# RFWBBoard.net
KiCad netlist of a schematic drawn in EAGLE
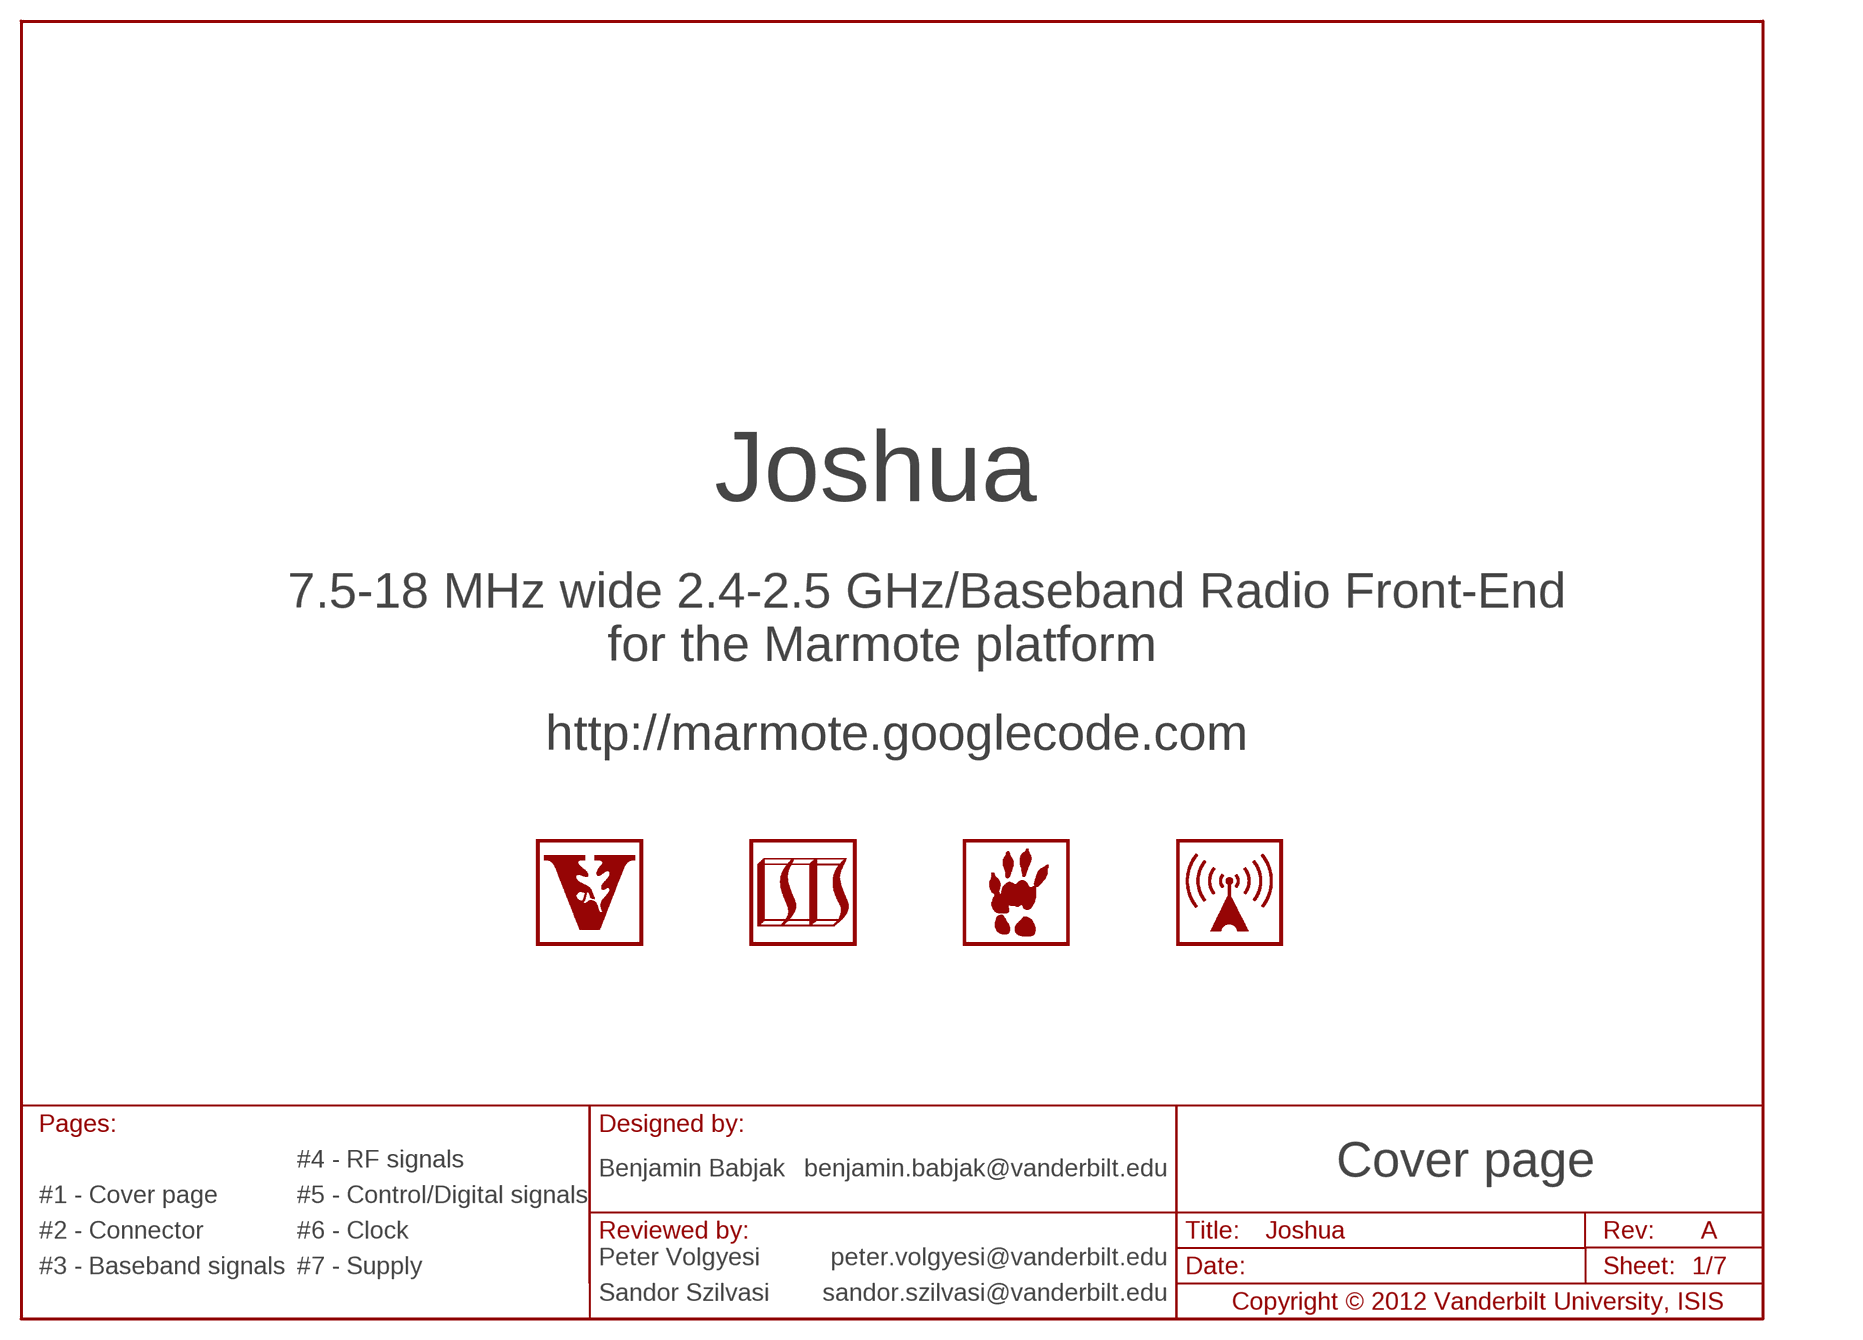
[diagram p0: schematic, sheet 1]
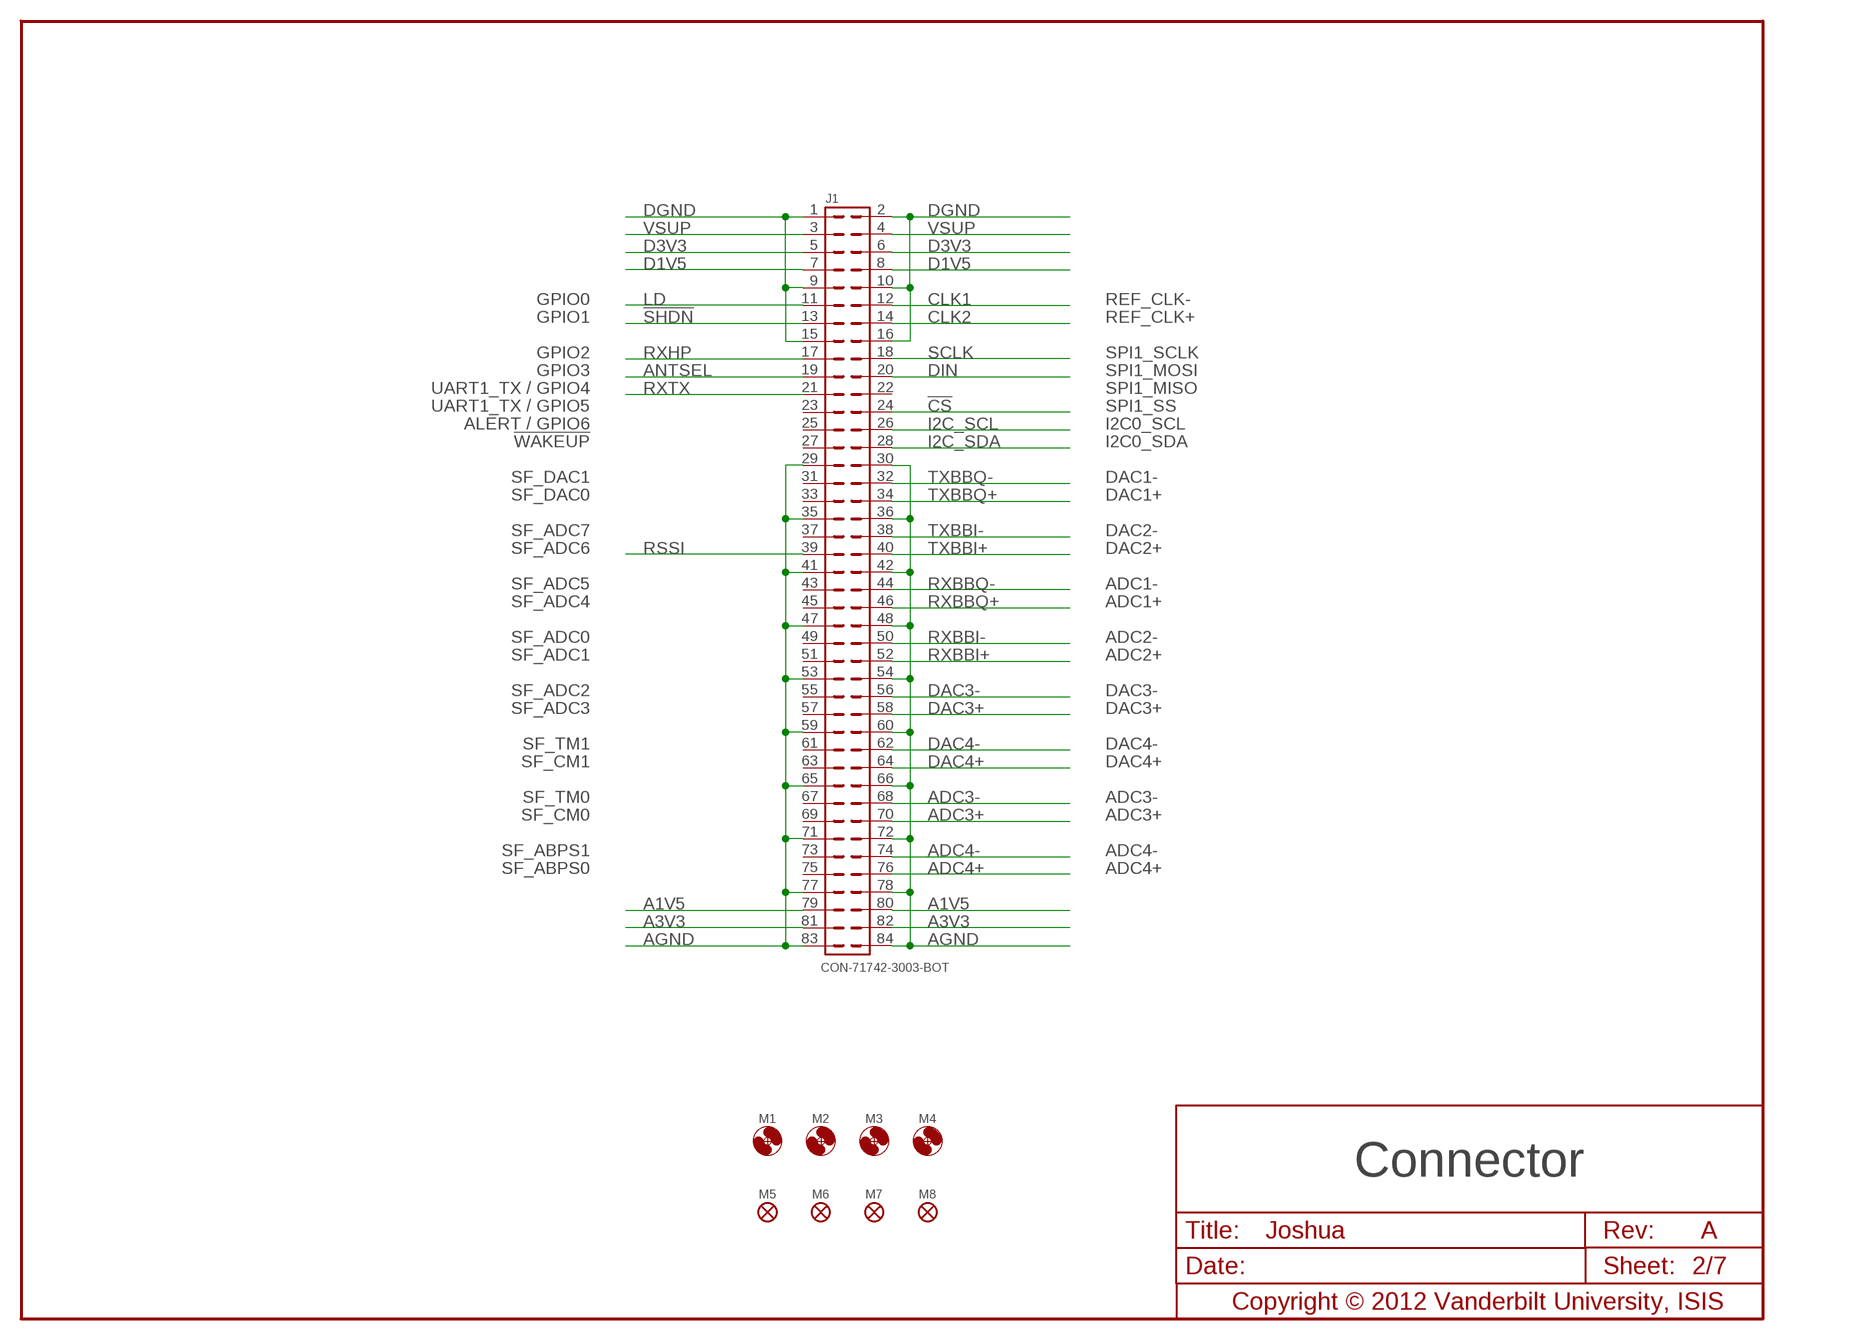
[diagram p1: schematic, sheet 2]
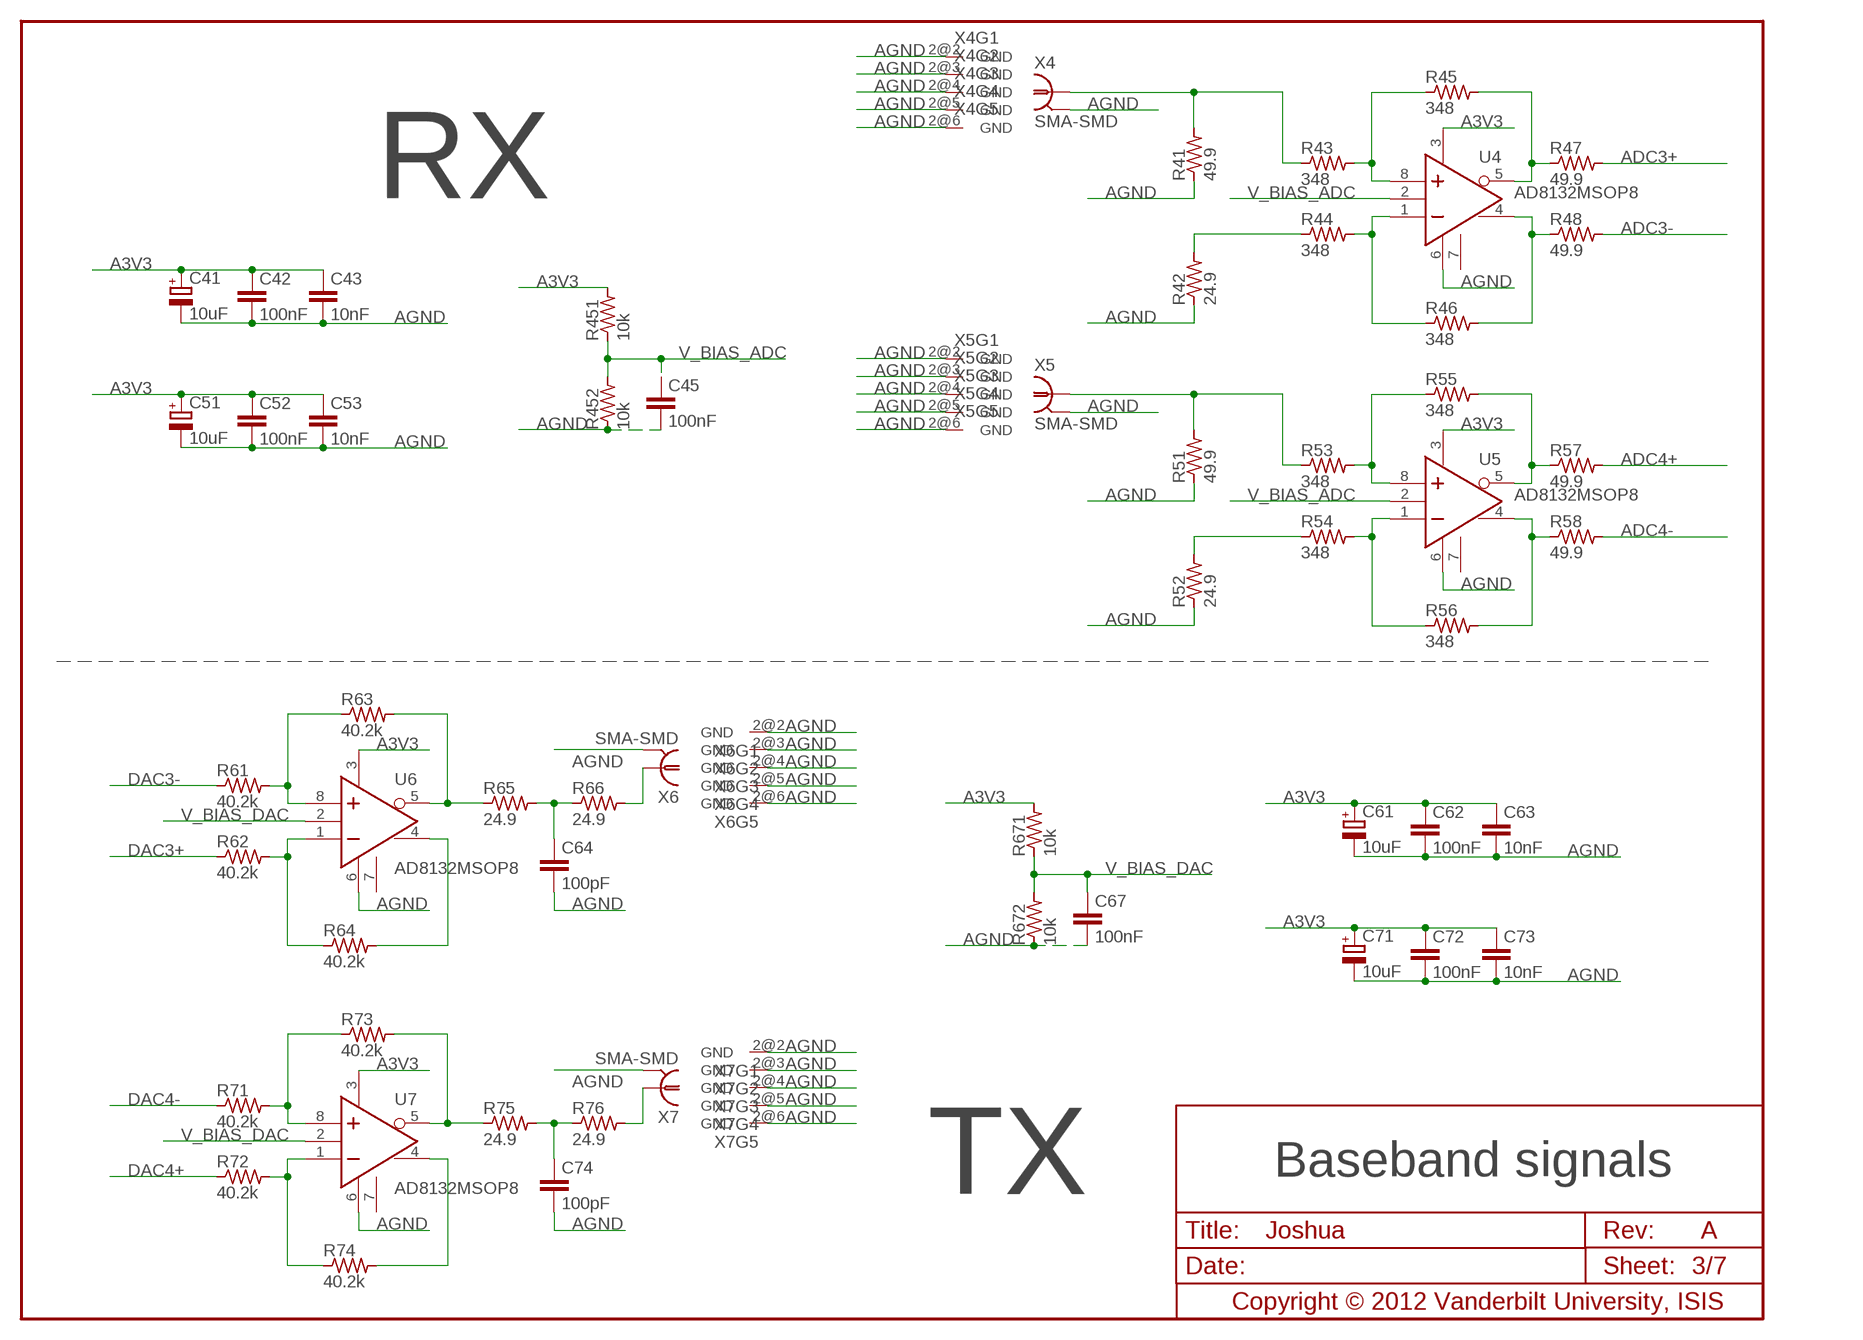
[diagram p2: schematic, sheet 3]
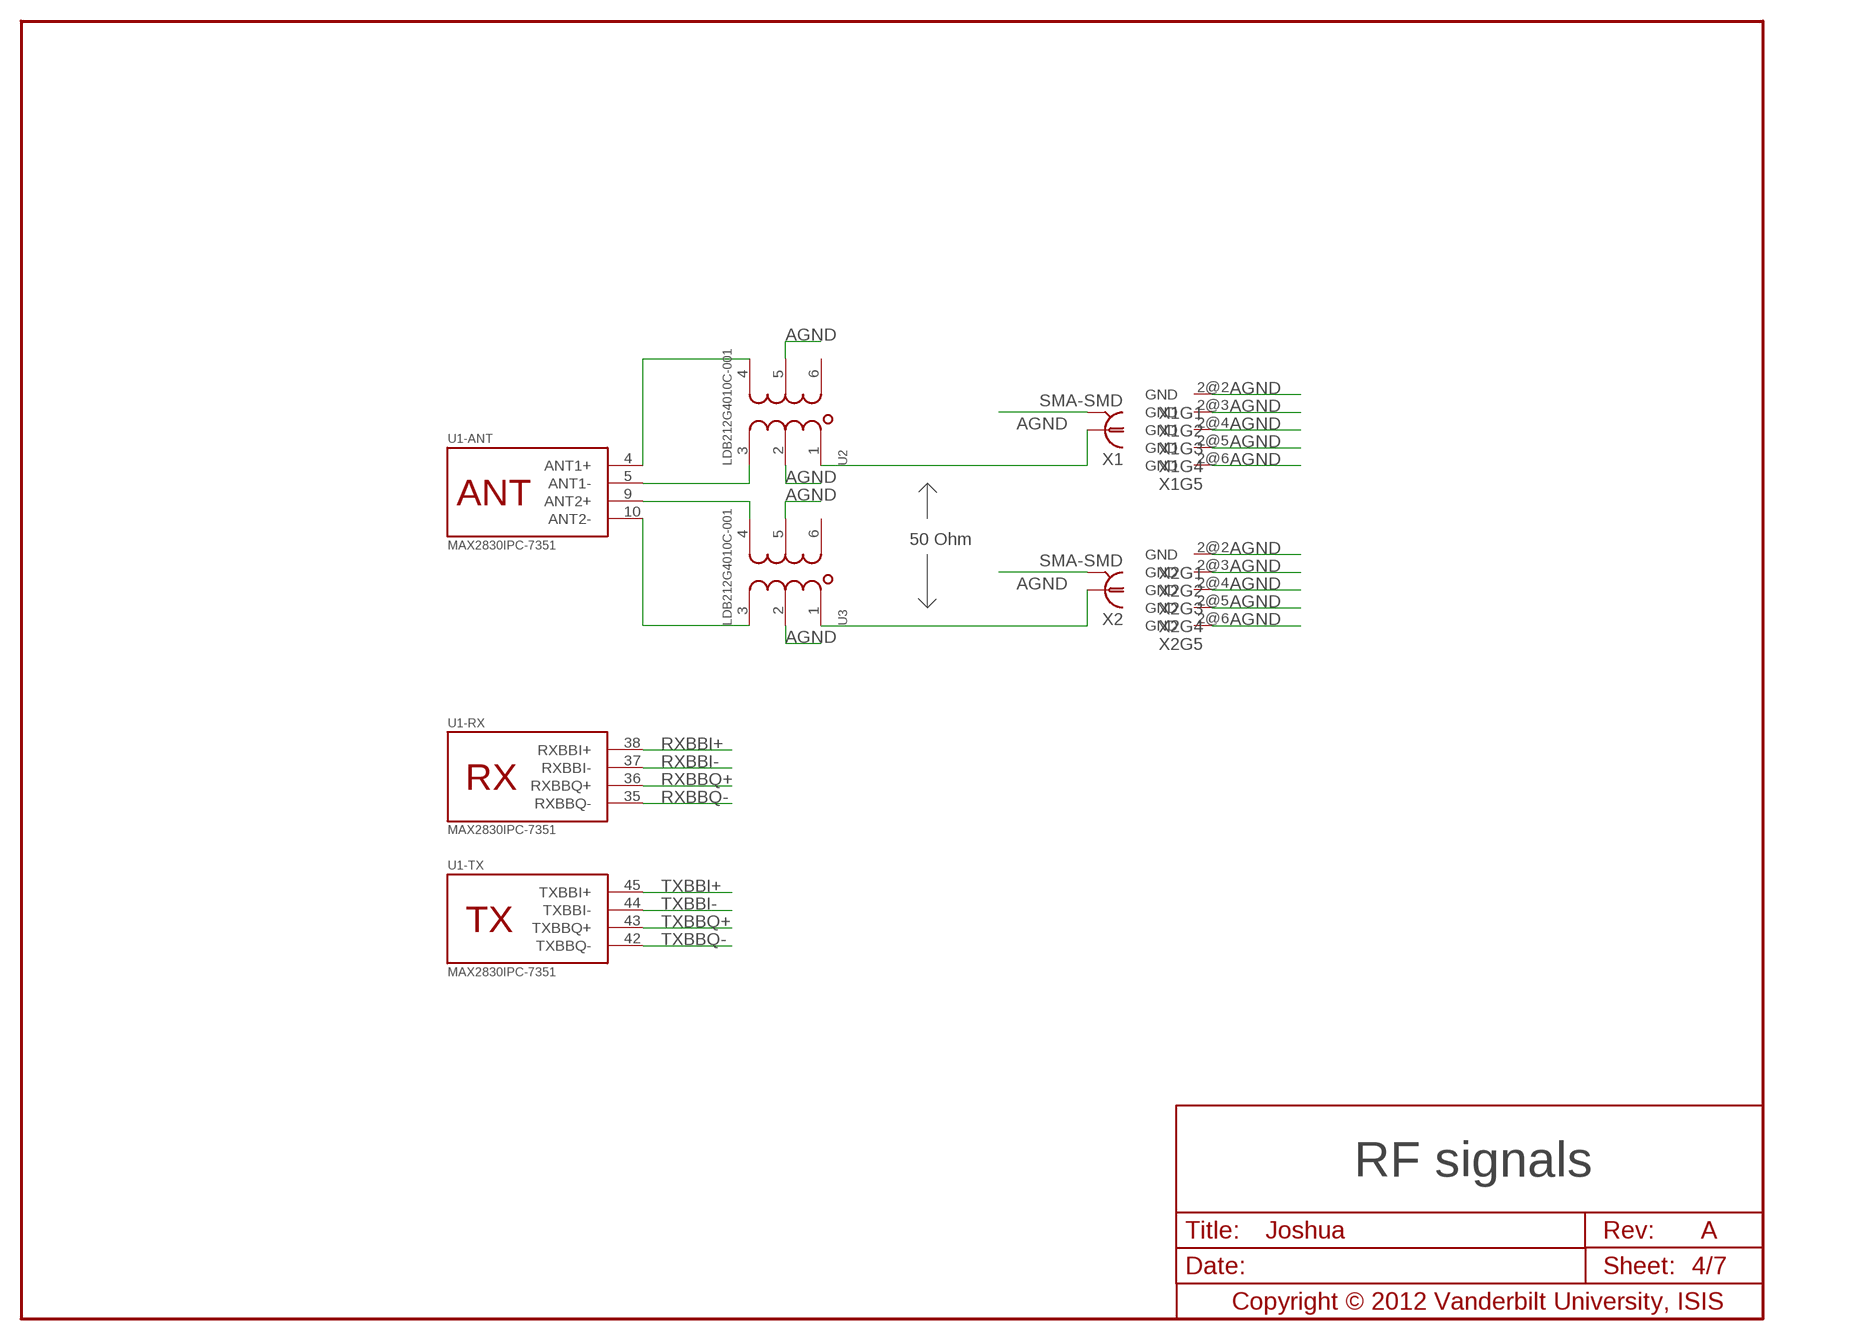
[diagram p3: schematic, sheet 4]
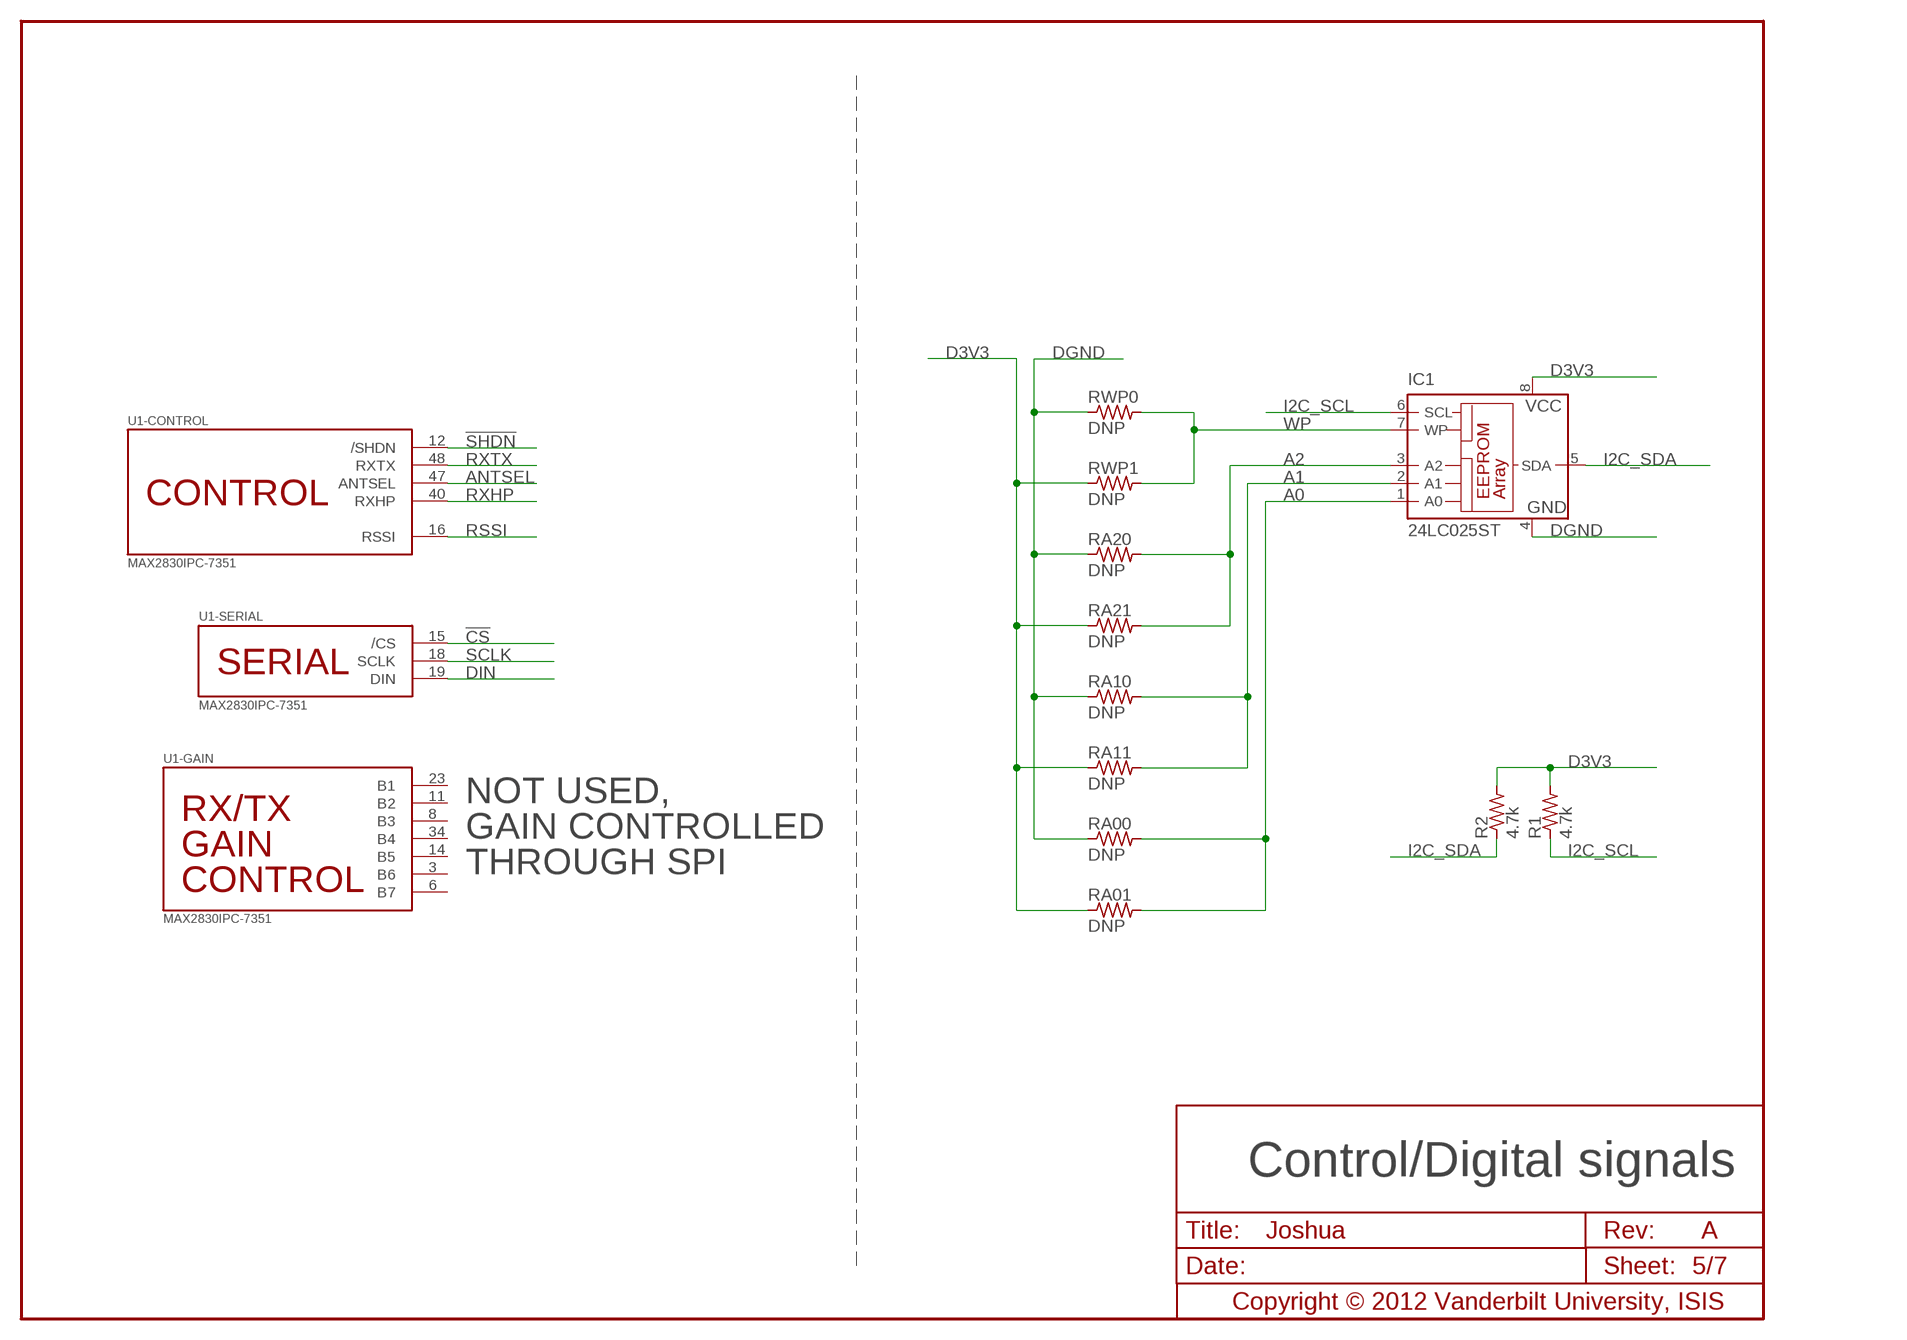
[diagram p4: schematic, sheet 5]
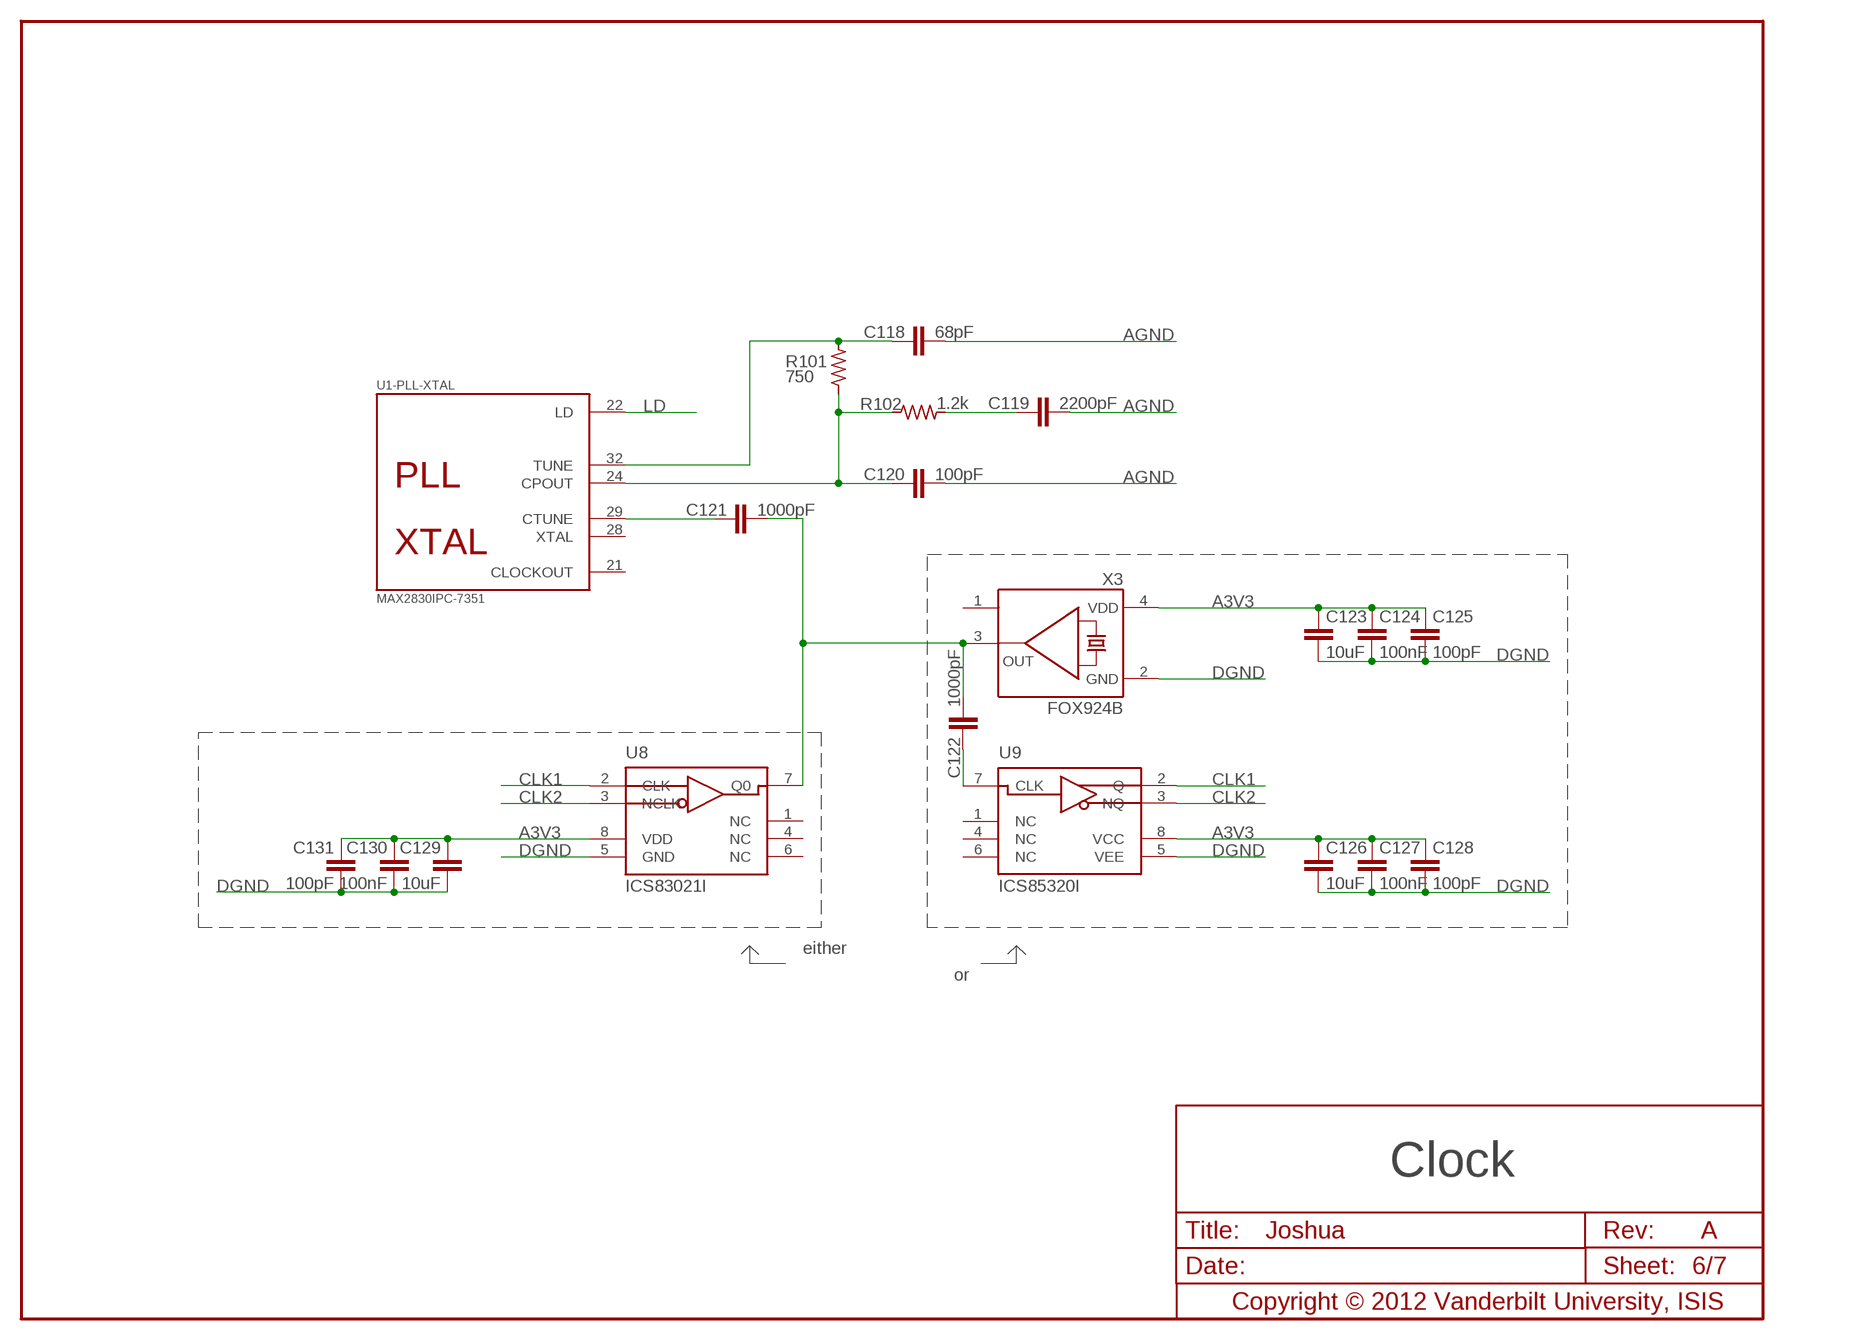
[diagram p5: schematic, sheet 6]
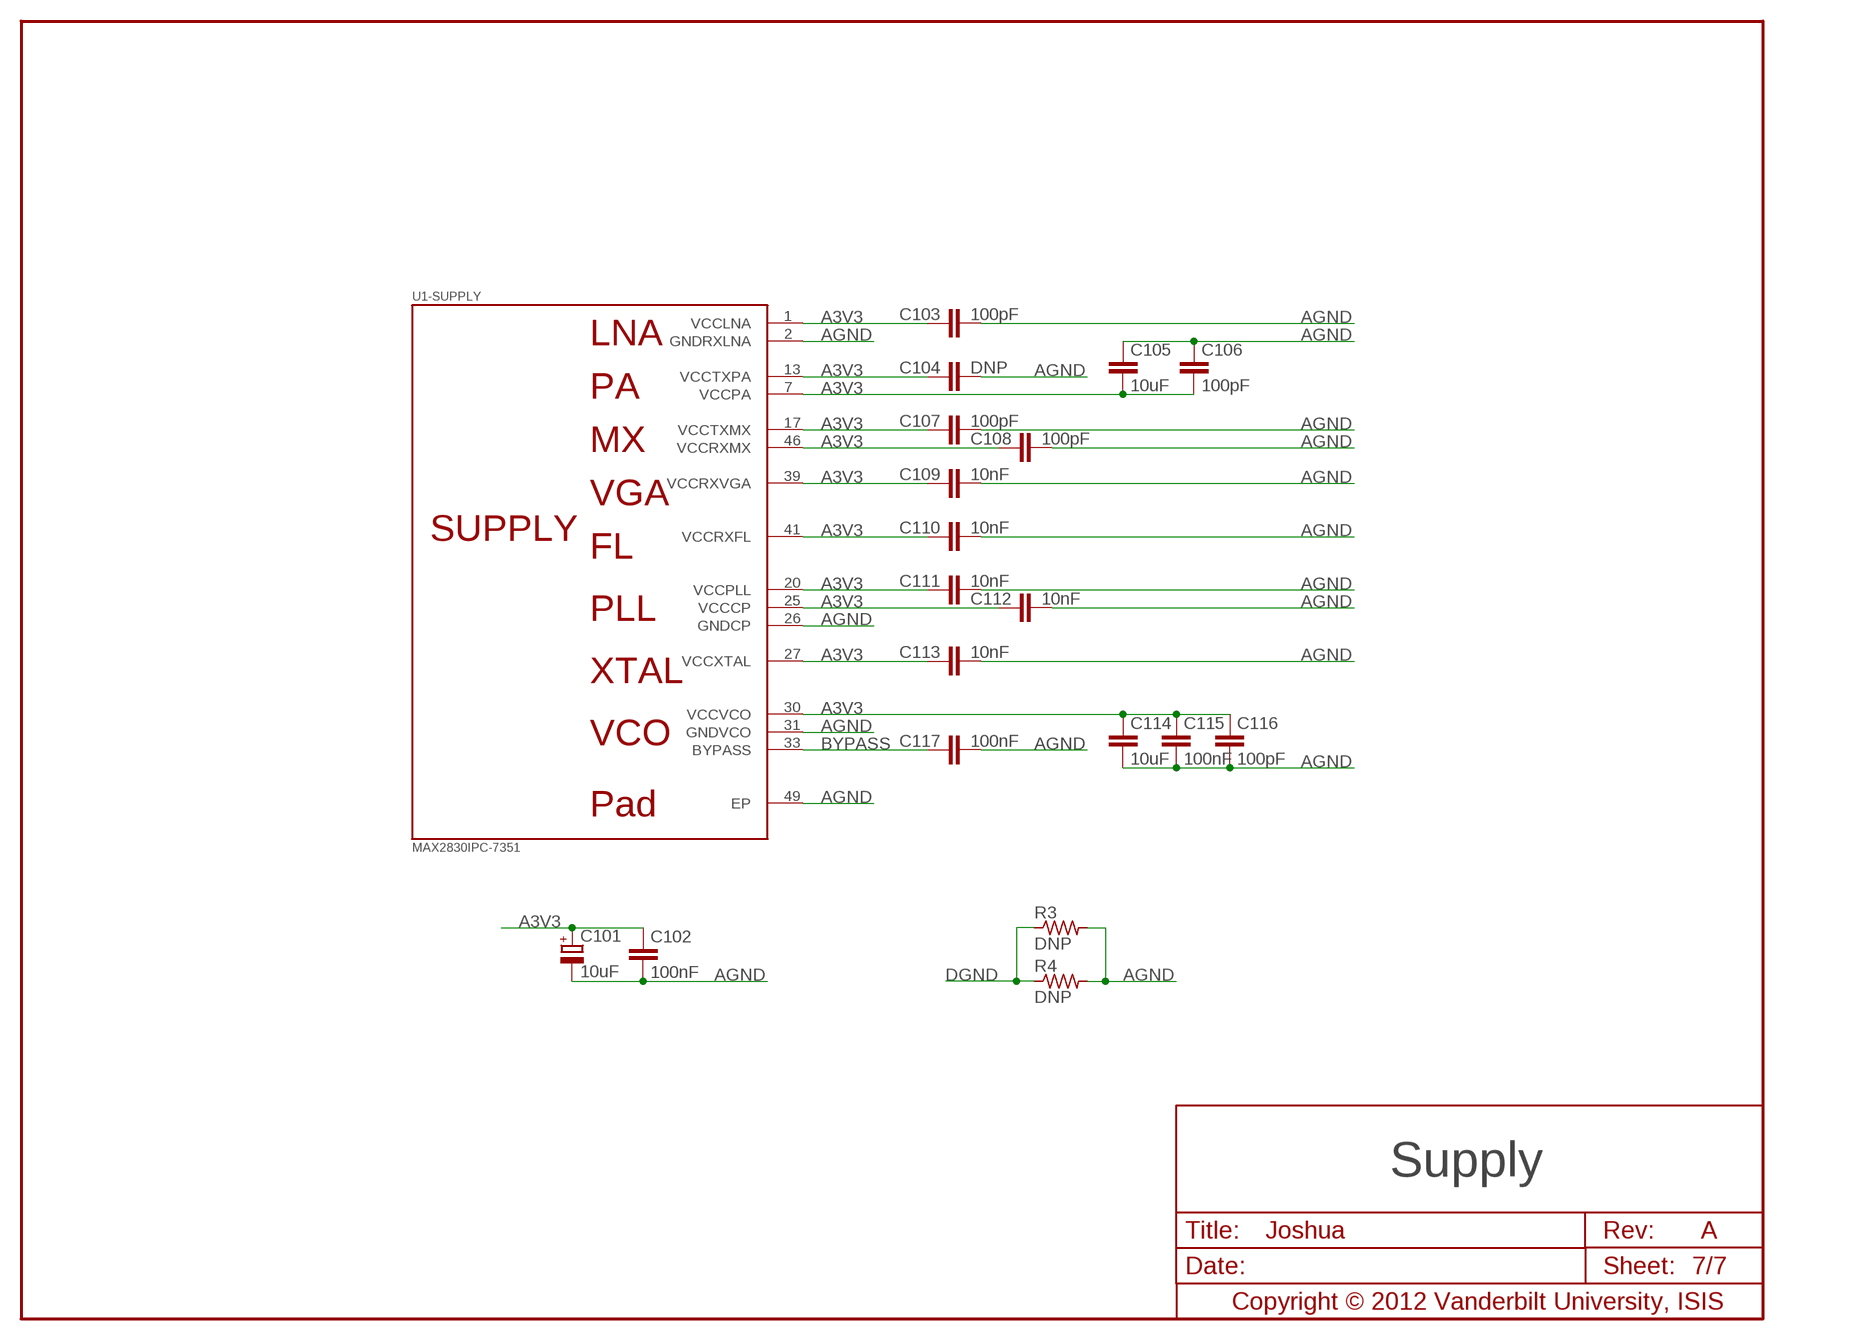
[diagram p6: schematic, sheet 7]

(export (version "E")
  (design (tool "Eeschema 10.0.6"))
  (components
    (comp (ref "J1")
      (value "CON-71742-3003-BOT")
      (footprint "eagle-import:71742-3003-BOT")
      (libsource (lib "eagle-import") (part "CON-71742-3003-BOT"))
    )
    (comp (ref "M1")
      (value "MOUNT-HOLE3.3")
      (footprint "eagle-import:3,3")
      (libsource (lib "eagle-import") (part "MOUNT-HOLE3.3"))
    )
    (comp (ref "M2")
      (value "MOUNT-HOLE3.3")
      (footprint "eagle-import:3,3")
      (libsource (lib "eagle-import") (part "MOUNT-HOLE3.3"))
    )
    (comp (ref "M3")
      (value "MOUNT-HOLE3.3")
      (footprint "eagle-import:3,3")
      (libsource (lib "eagle-import") (part "MOUNT-HOLE3.3"))
    )
    (comp (ref "M4")
      (value "MOUNT-HOLE3.3")
      (footprint "eagle-import:3,3")
      (libsource (lib "eagle-import") (part "MOUNT-HOLE3.3"))
    )
    (comp (ref "M5")
      (value "FIDUCIAL1X2")
      (footprint "eagle-import:FIDUCIAL-1X2")
      (libsource (lib "eagle-import") (part "FIDUCIAL1X2"))
    )
    (comp (ref "M6")
      (value "FIDUCIAL1X2")
      (footprint "eagle-import:FIDUCIAL-1X2")
      (libsource (lib "eagle-import") (part "FIDUCIAL1X2"))
    )
    (comp (ref "M7")
      (value "FIDUCIAL1X2")
      (footprint "eagle-import:FIDUCIAL-1X2")
      (libsource (lib "eagle-import") (part "FIDUCIAL1X2"))
    )
    (comp (ref "M8")
      (value "FIDUCIAL1X2")
      (footprint "eagle-import:FIDUCIAL-1X2")
      (libsource (lib "eagle-import") (part "FIDUCIAL1X2"))
    )
    (comp (ref "LOGO4")
      (value "LOGO-ISIS-600MIL-10MM-SS")
      (footprint "eagle-import:LOGO-ISIS-10MM-SILKSCREEN")
      (libsource (lib "eagle-import") (part "LOGO-ISIS-600MIL-10MM-SS"))
    )
    (comp (ref "LOGO5")
      (value "LOGO-VANDERBILT-600MIL-10MM-SS")
      (footprint "eagle-import:LOGO-VANDERBILT-10MM-SILKSCREEN")
      (libsource (lib "eagle-import") (part "LOGO-VANDERBILT-600MIL-10MM-SS"))
    )
    (comp (ref "LOGO6")
      (value "LOGO-MARMOTE-600MIL-10MM-SS")
      (footprint "eagle-import:LOGO-MARMOTE-10MM-SILKSCREEN")
      (libsource (lib "eagle-import") (part "LOGO-MARMOTE-600MIL-10MM-SS"))
    )
    (comp (ref "LOGO7")
      (value "LOGO-RADIO-3-600MIL-10MM-SS")
      (footprint "eagle-import:LOGO-RADIO-FILLED-10MM-SILKSCREEN")
      (libsource (lib "eagle-import") (part "LOGO-RADIO-3-600MIL-10MM-SS"))
    )
    (comp (ref "C41")
      (value "10uF")
      (footprint "eagle-import:CPOL2012")
      (libsource (lib "eagle-import") (part "CPOL2012"))
    )
    (comp (ref "C42")
      (value "100nF")
      (footprint "eagle-import:C0402")
      (libsource (lib "eagle-import") (part "C0402"))
    )
    (comp (ref "C43")
      (value "10nF")
      (footprint "eagle-import:C0402")
      (libsource (lib "eagle-import") (part "C0402"))
    )
    (comp (ref "C45")
      (value "100nF")
      (footprint "eagle-import:C0402")
      (libsource (lib "eagle-import") (part "C0402"))
    )
    (comp (ref "C51")
      (value "10uF")
      (footprint "eagle-import:CPOL2012")
      (libsource (lib "eagle-import") (part "CPOL2012"))
    )
    (comp (ref "C52")
      (value "100nF")
      (footprint "eagle-import:C0402")
      (libsource (lib "eagle-import") (part "C0402"))
    )
    (comp (ref "C53")
      (value "10nF")
      (footprint "eagle-import:C0402")
      (libsource (lib "eagle-import") (part "C0402"))
    )
    (comp (ref "C61")
      (value "10uF")
      (footprint "eagle-import:CPOL2012")
      (libsource (lib "eagle-import") (part "CPOL2012"))
    )
    (comp (ref "C62")
      (value "100nF")
      (footprint "eagle-import:C0402")
      (libsource (lib "eagle-import") (part "C0402"))
    )
    (comp (ref "C63")
      (value "10nF")
      (footprint "eagle-import:C0402")
      (libsource (lib "eagle-import") (part "C0402"))
    )
    (comp (ref "C64")
      (value "100pF")
      (footprint "eagle-import:C0402")
      (libsource (lib "eagle-import") (part "C0402"))
    )
    (comp (ref "C67")
      (value "100nF")
      (footprint "eagle-import:C0402")
      (libsource (lib "eagle-import") (part "C0402"))
    )
    (comp (ref "C71")
      (value "10uF")
      (footprint "eagle-import:CPOL2012")
      (libsource (lib "eagle-import") (part "CPOL2012"))
    )
    (comp (ref "C72")
      (value "100nF")
      (footprint "eagle-import:C0402")
      (libsource (lib "eagle-import") (part "C0402"))
    )
    (comp (ref "C73")
      (value "10nF")
      (footprint "eagle-import:C0402")
      (libsource (lib "eagle-import") (part "C0402"))
    )
    (comp (ref "C74")
      (value "100pF")
      (footprint "eagle-import:C0402")
      (libsource (lib "eagle-import") (part "C0402"))
    )
    (comp (ref "R41")
      (value "49.9")
      (footprint "eagle-import:R0402")
      (libsource (lib "eagle-import") (part "R0402"))
    )
    (comp (ref "R42")
      (value "24.9")
      (footprint "eagle-import:R0402")
      (libsource (lib "eagle-import") (part "R0402"))
    )
    (comp (ref "R43")
      (value "348")
      (footprint "eagle-import:R0402")
      (libsource (lib "eagle-import") (part "R0402"))
    )
    (comp (ref "R44")
      (value "348")
      (footprint "eagle-import:R0402")
      (libsource (lib "eagle-import") (part "R0402"))
    )
    (comp (ref "R45")
      (value "348")
      (footprint "eagle-import:R0402")
      (libsource (lib "eagle-import") (part "R0402"))
    )
    (comp (ref "R46")
      (value "348")
      (footprint "eagle-import:R0402")
      (libsource (lib "eagle-import") (part "R0402"))
    )
    (comp (ref "R47")
      (value "49.9")
      (footprint "eagle-import:R0402")
      (libsource (lib "eagle-import") (part "R0402"))
    )
    (comp (ref "R48")
      (value "49.9")
      (footprint "eagle-import:R0402")
      (libsource (lib "eagle-import") (part "R0402"))
    )
    (comp (ref "R51")
      (value "49.9")
      (footprint "eagle-import:R0402")
      (libsource (lib "eagle-import") (part "R0402"))
    )
    (comp (ref "R52")
      (value "24.9")
      (footprint "eagle-import:R0402")
      (libsource (lib "eagle-import") (part "R0402"))
    )
    (comp (ref "R53")
      (value "348")
      (footprint "eagle-import:R0402")
      (libsource (lib "eagle-import") (part "R0402"))
    )
    (comp (ref "R54")
      (value "348")
      (footprint "eagle-import:R0402")
      (libsource (lib "eagle-import") (part "R0402"))
    )
    (comp (ref "R55")
      (value "348")
      (footprint "eagle-import:R0402")
      (libsource (lib "eagle-import") (part "R0402"))
    )
    (comp (ref "R56")
      (value "348")
      (footprint "eagle-import:R0402")
      (libsource (lib "eagle-import") (part "R0402"))
    )
    (comp (ref "R57")
      (value "49.9")
      (footprint "eagle-import:R0402")
      (libsource (lib "eagle-import") (part "R0402"))
    )
    (comp (ref "R58")
      (value "49.9")
      (footprint "eagle-import:R0402")
      (libsource (lib "eagle-import") (part "R0402"))
    )
    (comp (ref "R61")
      (value "40.2k")
      (footprint "eagle-import:R0402")
      (libsource (lib "eagle-import") (part "R0402"))
    )
    (comp (ref "R62")
      (value "40.2k")
      (footprint "eagle-import:R0402")
      (libsource (lib "eagle-import") (part "R0402"))
    )
    (comp (ref "R63")
      (value "40.2k")
      (footprint "eagle-import:R0402")
      (libsource (lib "eagle-import") (part "R0402"))
    )
    (comp (ref "R64")
      (value "40.2k")
      (footprint "eagle-import:R0402")
      (libsource (lib "eagle-import") (part "R0402"))
    )
    (comp (ref "R65")
      (value "24.9")
      (footprint "eagle-import:R0402")
      (libsource (lib "eagle-import") (part "R0402"))
    )
    (comp (ref "R66")
      (value "24.9")
      (footprint "eagle-import:R0402")
      (libsource (lib "eagle-import") (part "R0402"))
    )
    (comp (ref "R71")
      (value "40.2k")
      (footprint "eagle-import:R0402")
      (libsource (lib "eagle-import") (part "R0402"))
    )
    (comp (ref "R72")
      (value "40.2k")
      (footprint "eagle-import:R0402")
      (libsource (lib "eagle-import") (part "R0402"))
    )
    (comp (ref "R73")
      (value "40.2k")
      (footprint "eagle-import:R0402")
      (libsource (lib "eagle-import") (part "R0402"))
    )
    (comp (ref "R74")
      (value "40.2k")
      (footprint "eagle-import:R0402")
      (libsource (lib "eagle-import") (part "R0402"))
    )
    (comp (ref "R75")
      (value "24.9")
      (footprint "eagle-import:R0402")
      (libsource (lib "eagle-import") (part "R0402"))
    )
    (comp (ref "R76")
      (value "24.9")
      (footprint "eagle-import:R0402")
      (libsource (lib "eagle-import") (part "R0402"))
    )
    (comp (ref "R451")
      (value "10k")
      (footprint "eagle-import:R0402")
      (libsource (lib "eagle-import") (part "R0402"))
    )
    (comp (ref "R452")
      (value "10k")
      (footprint "eagle-import:R0402")
      (libsource (lib "eagle-import") (part "R0402"))
    )
    (comp (ref "R671")
      (value "10k")
      (footprint "eagle-import:R0402")
      (libsource (lib "eagle-import") (part "R0402"))
    )
    (comp (ref "R672")
      (value "10k")
      (footprint "eagle-import:R0402")
      (libsource (lib "eagle-import") (part "R0402"))
    )
    (comp (ref "U4")
      (value "AD8132MSOP8")
      (footprint "eagle-import:MSOP8")
      (libsource (lib "eagle-import") (part "AD8132MSOP8"))
    )
    (comp (ref "U5")
      (value "AD8132MSOP8")
      (footprint "eagle-import:MSOP8")
      (libsource (lib "eagle-import") (part "AD8132MSOP8"))
    )
    (comp (ref "U6")
      (value "AD8132MSOP8")
      (footprint "eagle-import:MSOP8")
      (libsource (lib "eagle-import") (part "AD8132MSOP8"))
    )
    (comp (ref "U7")
      (value "AD8132MSOP8")
      (footprint "eagle-import:MSOP8")
      (libsource (lib "eagle-import") (part "AD8132MSOP8"))
    )
    (comp (ref "X4")
      (value "SMA-SMD")
      (footprint "eagle-import:SMA-SMD")
      (libsource (lib "eagle-import") (part "SMA-SMD"))
    )
    (comp (ref "X5")
      (value "SMA-SMD")
      (footprint "eagle-import:SMA-SMD")
      (libsource (lib "eagle-import") (part "SMA-SMD"))
    )
    (comp (ref "X6")
      (value "SMA-SMD")
      (footprint "eagle-import:SMA-SMD")
      (libsource (lib "eagle-import") (part "SMA-SMD"))
    )
    (comp (ref "X7")
      (value "SMA-SMD")
      (footprint "eagle-import:SMA-SMD")
      (libsource (lib "eagle-import") (part "SMA-SMD"))
    )
    (comp (ref "IC1")
      (value "24LC025ST")
      (footprint "eagle-import:TSSOP8")
      (fields (field (name "MF") "MICROCHIP") (field (name "MPN") "24LC025-I/ST"))
      (libsource (lib "eagle-import") (part "24STLC025"))
    )
    (comp (ref "R1")
      (value "4.7k")
      (footprint "eagle-import:R0402")
      (libsource (lib "eagle-import") (part "R0402"))
    )
    (comp (ref "R2")
      (value "4.7k")
      (footprint "eagle-import:R0402")
      (libsource (lib "eagle-import") (part "R0402"))
    )
    (comp (ref "RA00")
      (value "DNP")
      (footprint "eagle-import:R0402")
      (libsource (lib "eagle-import") (part "R0402"))
    )
    (comp (ref "RA01")
      (value "DNP")
      (footprint "eagle-import:R0402")
      (libsource (lib "eagle-import") (part "R0402"))
    )
    (comp (ref "RA10")
      (value "DNP")
      (footprint "eagle-import:R0402")
      (libsource (lib "eagle-import") (part "R0402"))
    )
    (comp (ref "RA11")
      (value "DNP")
      (footprint "eagle-import:R0402")
      (libsource (lib "eagle-import") (part "R0402"))
    )
    (comp (ref "RA20")
      (value "DNP")
      (footprint "eagle-import:R0402")
      (libsource (lib "eagle-import") (part "R0402"))
    )
    (comp (ref "RA21")
      (value "DNP")
      (footprint "eagle-import:R0402")
      (libsource (lib "eagle-import") (part "R0402"))
    )
    (comp (ref "RWP0")
      (value "DNP")
      (footprint "eagle-import:R0402")
      (libsource (lib "eagle-import") (part "R0402"))
    )
    (comp (ref "RWP1")
      (value "DNP")
      (footprint "eagle-import:R0402")
      (libsource (lib "eagle-import") (part "R0402"))
    )
    (comp (ref "U1")
      (value "MAX2830IPC-7351")
      (footprint "eagle-import:TQFN-48")
      (libsource (lib "eagle-import") (part "MAX2830IPC-7351"))
    )
    (comp (ref "C118")
      (value "68pF")
      (footprint "eagle-import:C0402")
      (libsource (lib "eagle-import") (part "C0402"))
    )
    (comp (ref "C119")
      (value "2200pF")
      (footprint "eagle-import:C0402")
      (libsource (lib "eagle-import") (part "C0402"))
    )
    (comp (ref "C120")
      (value "100pF")
      (footprint "eagle-import:C0402")
      (libsource (lib "eagle-import") (part "C0402"))
    )
    (comp (ref "C121")
      (value "1000pF")
      (footprint "eagle-import:C0402")
      (libsource (lib "eagle-import") (part "C0402"))
    )
    (comp (ref "C122")
      (value "1000pF")
      (footprint "eagle-import:C0402")
      (libsource (lib "eagle-import") (part "C0402"))
    )
    (comp (ref "C123")
      (value "10uF")
      (footprint "eagle-import:C0805")
      (libsource (lib "eagle-import") (part "C0805"))
    )
    (comp (ref "C124")
      (value "100nF")
      (footprint "eagle-import:C0402")
      (libsource (lib "eagle-import") (part "C0402"))
    )
    (comp (ref "C125")
      (value "100pF")
      (footprint "eagle-import:C0402")
      (libsource (lib "eagle-import") (part "C0402"))
    )
    (comp (ref "C126")
      (value "10uF")
      (footprint "eagle-import:C0805")
      (libsource (lib "eagle-import") (part "C0805"))
    )
    (comp (ref "C127")
      (value "100nF")
      (footprint "eagle-import:C0402")
      (libsource (lib "eagle-import") (part "C0402"))
    )
    (comp (ref "C128")
      (value "100pF")
      (footprint "eagle-import:C0402")
      (libsource (lib "eagle-import") (part "C0402"))
    )
    (comp (ref "C129")
      (value "10uF")
      (footprint "eagle-import:C0805")
      (libsource (lib "eagle-import") (part "C0805"))
    )
    (comp (ref "C130")
      (value "100nF")
      (footprint "eagle-import:C0402")
      (libsource (lib "eagle-import") (part "C0402"))
    )
    (comp (ref "C131")
      (value "100pF")
      (footprint "eagle-import:C0402")
      (libsource (lib "eagle-import") (part "C0402"))
    )
    (comp (ref "R101")
      (value "750")
      (footprint "eagle-import:R0402")
      (libsource (lib "eagle-import") (part "R0402"))
    )
    (comp (ref "R102")
      (value "1.2k")
      (footprint "eagle-import:R0402")
      (libsource (lib "eagle-import") (part "R0402"))
    )
    (comp (ref "U8")
      (value "ICS83021I")
      (footprint "eagle-import:SOIC8")
      (libsource (lib "eagle-import") (part "ICS83021I"))
    )
    (comp (ref "U9")
      (value "ICS85320I")
      (footprint "eagle-import:SOIC8")
      (libsource (lib "eagle-import") (part "ICS85320I"))
    )
    (comp (ref "X3")
      (value "FOX924B")
      (footprint "eagle-import:FOX924")
      (fields (field (name "MF") "Fox Electronics") (field (name "MPN") "FOX924B-20.000"))
      (libsource (lib "eagle-import") (part "FOX924B"))
    )
    (comp (ref "U2")
      (value "LDB212G4010C-001")
      (footprint "eagle-import:LDB21-FOOTPRINT")
      (libsource (lib "eagle-import") (part "LDB212G4010C-001"))
    )
    (comp (ref "U3")
      (value "LDB212G4010C-001")
      (footprint "eagle-import:LDB21-FOOTPRINT")
      (libsource (lib "eagle-import") (part "LDB212G4010C-001"))
    )
    (comp (ref "X1")
      (value "SMA-SMD")
      (footprint "eagle-import:SMA-SMD")
      (libsource (lib "eagle-import") (part "SMA-SMD"))
    )
    (comp (ref "X2")
      (value "SMA-SMD")
      (footprint "eagle-import:SMA-SMD")
      (libsource (lib "eagle-import") (part "SMA-SMD"))
    )
    (comp (ref "C101")
      (value "10uF")
      (footprint "eagle-import:CPOL2012")
      (libsource (lib "eagle-import") (part "CPOL2012"))
    )
    (comp (ref "C102")
      (value "100nF")
      (footprint "eagle-import:C0402")
      (libsource (lib "eagle-import") (part "C0402"))
    )
    (comp (ref "C103")
      (value "100pF")
      (footprint "eagle-import:C0402")
      (libsource (lib "eagle-import") (part "C0402"))
    )
    (comp (ref "C104")
      (value "DNP")
      (footprint "eagle-import:C0402")
      (libsource (lib "eagle-import") (part "C0402"))
    )
    (comp (ref "C105")
      (value "10uF")
      (footprint "eagle-import:C1206")
      (libsource (lib "eagle-import") (part "C1206"))
    )
    (comp (ref "C106")
      (value "100pF")
      (footprint "eagle-import:C0402")
      (libsource (lib "eagle-import") (part "C0402"))
    )
    (comp (ref "C107")
      (value "100pF")
      (footprint "eagle-import:C0402")
      (libsource (lib "eagle-import") (part "C0402"))
    )
    (comp (ref "C108")
      (value "100pF")
      (footprint "eagle-import:C0402")
      (libsource (lib "eagle-import") (part "C0402"))
    )
    (comp (ref "C109")
      (value "10nF")
      (footprint "eagle-import:C0402")
      (libsource (lib "eagle-import") (part "C0402"))
    )
    (comp (ref "C110")
      (value "10nF")
      (footprint "eagle-import:C0402")
      (libsource (lib "eagle-import") (part "C0402"))
    )
    (comp (ref "C111")
      (value "10nF")
      (footprint "eagle-import:C0402")
      (libsource (lib "eagle-import") (part "C0402"))
    )
    (comp (ref "C112")
      (value "10nF")
      (footprint "eagle-import:C0402")
      (libsource (lib "eagle-import") (part "C0402"))
    )
    (comp (ref "C113")
      (value "10nF")
      (footprint "eagle-import:C0402")
      (libsource (lib "eagle-import") (part "C0402"))
    )
    (comp (ref "C114")
      (value "10uF")
      (footprint "eagle-import:C0805")
      (libsource (lib "eagle-import") (part "C0805"))
    )
    (comp (ref "C115")
      (value "100nF")
      (footprint "eagle-import:C0402")
      (libsource (lib "eagle-import") (part "C0402"))
    )
    (comp (ref "C116")
      (value "100pF")
      (footprint "eagle-import:C0402")
      (libsource (lib "eagle-import") (part "C0402"))
    )
    (comp (ref "C117")
      (value "100nF")
      (footprint "eagle-import:C0402")
      (libsource (lib "eagle-import") (part "C0402"))
    )
    (comp (ref "R3")
      (value "DNP")
      (footprint "eagle-import:R0603")
      (libsource (lib "eagle-import") (part "R0603"))
    )
    (comp (ref "R4")
      (value "DNP")
      (footprint "eagle-import:R0603")
      (libsource (lib "eagle-import") (part "R0603"))
    )
  )
  (nets
    (net (code "1") (name "A0") (class "Default")
      (node (ref "IC1") (pin "1") (pinfunction "A0_1") (pintype "input"))
      (node (ref "RA00") (pin "2") (pinfunction "2_2") (pintype "passive"))
      (node (ref "RA01") (pin "2") (pinfunction "2_2") (pintype "passive"))
    )
    (net (code "2") (name "A1") (class "Default")
      (node (ref "IC1") (pin "2") (pinfunction "A1_2") (pintype "input"))
      (node (ref "RA10") (pin "2") (pinfunction "2_2") (pintype "passive"))
      (node (ref "RA11") (pin "2") (pinfunction "2_2") (pintype "passive"))
    )
    (net (code "3") (name "A1V5") (class "Default")
      (node (ref "J1") (pin "79") (pinfunction "79_79") (pintype "passive"))
      (node (ref "J1") (pin "80") (pinfunction "80_80") (pintype "passive"))
    )
    (net (code "4") (name "A2") (class "Default")
      (node (ref "IC1") (pin "3") (pinfunction "A2_3") (pintype "input"))
      (node (ref "RA20") (pin "2") (pinfunction "2_2") (pintype "passive"))
      (node (ref "RA21") (pin "2") (pinfunction "2_2") (pintype "passive"))
    )
    (net (code "5") (name "A3V3") (class "Default")
      (node (ref "C101") (pin "+") (pinfunction "+_+") (pintype "passive"))
      (node (ref "C102") (pin "1") (pinfunction "1_1") (pintype "passive"))
      (node (ref "C103") (pin "1") (pinfunction "1_1") (pintype "passive"))
      (node (ref "C104") (pin "1") (pinfunction "1_1") (pintype "passive"))
      (node (ref "C105") (pin "2") (pinfunction "2_2") (pintype "passive"))
      (node (ref "C106") (pin "2") (pinfunction "2_2") (pintype "passive"))
      (node (ref "C107") (pin "1") (pinfunction "1_1") (pintype "passive"))
      (node (ref "C108") (pin "1") (pinfunction "1_1") (pintype "passive"))
      (node (ref "C109") (pin "1") (pinfunction "1_1") (pintype "passive"))
      (node (ref "C110") (pin "1") (pinfunction "1_1") (pintype "passive"))
      (node (ref "C111") (pin "1") (pinfunction "1_1") (pintype "passive"))
      (node (ref "C112") (pin "1") (pinfunction "1_1") (pintype "passive"))
      (node (ref "C113") (pin "1") (pinfunction "1_1") (pintype "passive"))
      (node (ref "C114") (pin "1") (pinfunction "1_1") (pintype "passive"))
      (node (ref "C115") (pin "1") (pinfunction "1_1") (pintype "passive"))
      (node (ref "C116") (pin "1") (pinfunction "1_1") (pintype "passive"))
      (node (ref "C123") (pin "1") (pinfunction "1_1") (pintype "passive"))
      (node (ref "C124") (pin "1") (pinfunction "1_1") (pintype "passive"))
      (node (ref "C125") (pin "1") (pinfunction "1_1") (pintype "passive"))
      (node (ref "C126") (pin "1") (pinfunction "1_1") (pintype "passive"))
      (node (ref "C127") (pin "1") (pinfunction "1_1") (pintype "passive"))
      (node (ref "C128") (pin "1") (pinfunction "1_1") (pintype "passive"))
      (node (ref "C129") (pin "1") (pinfunction "1_1") (pintype "passive"))
      (node (ref "C130") (pin "1") (pinfunction "1_1") (pintype "passive"))
      (node (ref "C131") (pin "1") (pinfunction "1_1") (pintype "passive"))
      (node (ref "C41") (pin "+") (pinfunction "+_+") (pintype "passive"))
      (node (ref "C42") (pin "1") (pinfunction "1_1") (pintype "passive"))
      (node (ref "C43") (pin "1") (pinfunction "1_1") (pintype "passive"))
      (node (ref "C51") (pin "+") (pinfunction "+_+") (pintype "passive"))
      (node (ref "C52") (pin "1") (pinfunction "1_1") (pintype "passive"))
      (node (ref "C53") (pin "1") (pinfunction "1_1") (pintype "passive"))
      (node (ref "C61") (pin "+") (pinfunction "+_+") (pintype "passive"))
      (node (ref "C62") (pin "1") (pinfunction "1_1") (pintype "passive"))
      (node (ref "C63") (pin "1") (pinfunction "1_1") (pintype "passive"))
      (node (ref "C71") (pin "+") (pinfunction "+_+") (pintype "passive"))
      (node (ref "C72") (pin "1") (pinfunction "1_1") (pintype "passive"))
      (node (ref "C73") (pin "1") (pinfunction "1_1") (pintype "passive"))
      (node (ref "J1") (pin "81") (pinfunction "81_81") (pintype "passive"))
      (node (ref "J1") (pin "82") (pinfunction "82_82") (pintype "passive"))
      (node (ref "R451") (pin "2") (pinfunction "2_2") (pintype "passive"))
      (node (ref "R671") (pin "2") (pinfunction "2_2") (pintype "passive"))
      (node (ref "U1") (pin "1") (pinfunction "VCCLNA_1") (pintype "power_in"))
      (node (ref "U1") (pin "13") (pinfunction "VCCTXPA_13") (pintype "power_in"))
      (node (ref "U1") (pin "17") (pinfunction "VCCTXMX_17") (pintype "power_in"))
      (node (ref "U1") (pin "20") (pinfunction "VCCPLL_20") (pintype "power_in"))
      (node (ref "U1") (pin "25") (pinfunction "VCCCP_25") (pintype "power_in"))
      (node (ref "U1") (pin "27") (pinfunction "VCCXTAL_27") (pintype "power_in"))
      (node (ref "U1") (pin "30") (pinfunction "VCCVCO_30") (pintype "power_in"))
      (node (ref "U1") (pin "39") (pinfunction "VCCRXVGA_39") (pintype "power_in"))
      (node (ref "U1") (pin "41") (pinfunction "VCCRXFL_41") (pintype "power_in"))
      (node (ref "U1") (pin "46") (pinfunction "VCCRXMX_46") (pintype "power_in"))
      (node (ref "U1") (pin "7") (pinfunction "VCCPA_7") (pintype "power_in"))
      (node (ref "U4") (pin "3") (pinfunction "V_S+_3") (pintype "power_in"))
      (node (ref "U5") (pin "3") (pinfunction "V_S+_3") (pintype "power_in"))
      (node (ref "U6") (pin "3") (pinfunction "V_S+_3") (pintype "power_in"))
      (node (ref "U7") (pin "3") (pinfunction "V_S+_3") (pintype "power_in"))
      (node (ref "U8") (pin "8") (pinfunction "VDD_8") (pintype "power_in"))
      (node (ref "U9") (pin "8") (pinfunction "VCC_8") (pintype "power_in"))
      (node (ref "X3") (pin "4") (pinfunction "VCC_4") (pintype "power_in"))
    )
    (net (code "6") (name "ADC3+") (class "Default")
      (node (ref "J1") (pin "70") (pinfunction "70_70") (pintype "passive"))
      (node (ref "R47") (pin "2") (pinfunction "2_2") (pintype "passive"))
    )
    (net (code "7") (name "ADC3-") (class "Default")
      (node (ref "J1") (pin "68") (pinfunction "68_68") (pintype "passive"))
      (node (ref "R48") (pin "2") (pinfunction "2_2") (pintype "passive"))
    )
    (net (code "8") (name "ADC4+") (class "Default")
      (node (ref "J1") (pin "76") (pinfunction "76_76") (pintype "passive"))
      (node (ref "R57") (pin "2") (pinfunction "2_2") (pintype "passive"))
    )
    (net (code "9") (name "ADC4-") (class "Default")
      (node (ref "J1") (pin "74") (pinfunction "74_74") (pintype "passive"))
      (node (ref "R58") (pin "2") (pinfunction "2_2") (pintype "passive"))
    )
    (net (code "10") (name "AGND") (class "Default")
      (node (ref "C101") (pin "-") (pinfunction "-_-") (pintype "passive"))
      (node (ref "C102") (pin "2") (pinfunction "2_2") (pintype "passive"))
      (node (ref "C103") (pin "2") (pinfunction "2_2") (pintype "passive"))
      (node (ref "C104") (pin "2") (pinfunction "2_2") (pintype "passive"))
      (node (ref "C105") (pin "1") (pinfunction "1_1") (pintype "passive"))
      (node (ref "C106") (pin "1") (pinfunction "1_1") (pintype "passive"))
      (node (ref "C107") (pin "2") (pinfunction "2_2") (pintype "passive"))
      (node (ref "C108") (pin "2") (pinfunction "2_2") (pintype "passive"))
      (node (ref "C109") (pin "2") (pinfunction "2_2") (pintype "passive"))
      (node (ref "C110") (pin "2") (pinfunction "2_2") (pintype "passive"))
      (node (ref "C111") (pin "2") (pinfunction "2_2") (pintype "passive"))
      (node (ref "C112") (pin "2") (pinfunction "2_2") (pintype "passive"))
      (node (ref "C113") (pin "2") (pinfunction "2_2") (pintype "passive"))
      (node (ref "C114") (pin "2") (pinfunction "2_2") (pintype "passive"))
      (node (ref "C115") (pin "2") (pinfunction "2_2") (pintype "passive"))
      (node (ref "C116") (pin "2") (pinfunction "2_2") (pintype "passive"))
      (node (ref "C117") (pin "2") (pinfunction "2_2") (pintype "passive"))
      (node (ref "C118") (pin "2") (pinfunction "2_2") (pintype "passive"))
      (node (ref "C119") (pin "2") (pinfunction "2_2") (pintype "passive"))
      (node (ref "C120") (pin "2") (pinfunction "2_2") (pintype "passive"))
      (node (ref "C41") (pin "-") (pinfunction "-_-") (pintype "passive"))
      (node (ref "C42") (pin "2") (pinfunction "2_2") (pintype "passive"))
      (node (ref "C43") (pin "2") (pinfunction "2_2") (pintype "passive"))
      (node (ref "C45") (pin "2") (pinfunction "2_2") (pintype "passive"))
      (node (ref "C51") (pin "-") (pinfunction "-_-") (pintype "passive"))
      (node (ref "C52") (pin "2") (pinfunction "2_2") (pintype "passive"))
      (node (ref "C53") (pin "2") (pinfunction "2_2") (pintype "passive"))
      (node (ref "C61") (pin "-") (pinfunction "-_-") (pintype "passive"))
      (node (ref "C62") (pin "2") (pinfunction "2_2") (pintype "passive"))
      (node (ref "C63") (pin "2") (pinfunction "2_2") (pintype "passive"))
      (node (ref "C64") (pin "2") (pinfunction "2_2") (pintype "passive"))
      (node (ref "C67") (pin "2") (pinfunction "2_2") (pintype "passive"))
      (node (ref "C71") (pin "-") (pinfunction "-_-") (pintype "passive"))
      (node (ref "C72") (pin "2") (pinfunction "2_2") (pintype "passive"))
      (node (ref "C73") (pin "2") (pinfunction "2_2") (pintype "passive"))
      (node (ref "C74") (pin "2") (pinfunction "2_2") (pintype "passive"))
      (node (ref "J1") (pin "29") (pinfunction "29_29") (pintype "passive"))
      (node (ref "J1") (pin "30") (pinfunction "30_30") (pintype "passive"))
      (node (ref "J1") (pin "35") (pinfunction "35_35") (pintype "passive"))
      (node (ref "J1") (pin "36") (pinfunction "36_36") (pintype "passive"))
      (node (ref "J1") (pin "41") (pinfunction "41_41") (pintype "passive"))
      (node (ref "J1") (pin "42") (pinfunction "42_42") (pintype "passive"))
      (node (ref "J1") (pin "47") (pinfunction "47_47") (pintype "passive"))
      (node (ref "J1") (pin "48") (pinfunction "48_48") (pintype "passive"))
      (node (ref "J1") (pin "53") (pinfunction "53_53") (pintype "passive"))
      (node (ref "J1") (pin "54") (pinfunction "54_54") (pintype "passive"))
      (node (ref "J1") (pin "59") (pinfunction "59_59") (pintype "passive"))
      (node (ref "J1") (pin "60") (pinfunction "60_60") (pintype "passive"))
      (node (ref "J1") (pin "65") (pinfunction "65_65") (pintype "passive"))
      (node (ref "J1") (pin "66") (pinfunction "66_66") (pintype "passive"))
      (node (ref "J1") (pin "71") (pinfunction "71_71") (pintype "passive"))
      (node (ref "J1") (pin "72") (pinfunction "72_72") (pintype "passive"))
      (node (ref "J1") (pin "77") (pinfunction "77_77") (pintype "passive"))
      (node (ref "J1") (pin "78") (pinfunction "78_78") (pintype "passive"))
      (node (ref "J1") (pin "83") (pinfunction "83_83") (pintype "passive"))
      (node (ref "J1") (pin "84") (pinfunction "84_84") (pintype "passive"))
      (node (ref "R3") (pin "2") (pinfunction "2_2") (pintype "passive"))
      (node (ref "R4") (pin "2") (pinfunction "2_2") (pintype "passive"))
      (node (ref "R41") (pin "1") (pinfunction "1_1") (pintype "passive"))
      (node (ref "R42") (pin "1") (pinfunction "1_1") (pintype "passive"))
      (node (ref "R452") (pin "1") (pinfunction "1_1") (pintype "passive"))
      (node (ref "R51") (pin "1") (pinfunction "1_1") (pintype "passive"))
      (node (ref "R52") (pin "1") (pinfunction "1_1") (pintype "passive"))
      (node (ref "R672") (pin "1") (pinfunction "1_1") (pintype "passive"))
      (node (ref "U1") (pin "2") (pinfunction "GNDRXLNA_2") (pintype "power_in"))
      (node (ref "U1") (pin "26") (pinfunction "GNDCP_26") (pintype "power_in"))
      (node (ref "U1") (pin "31") (pinfunction "GNDVCO_31") (pintype "power_in"))
      (node (ref "U1") (pin "49") (pinfunction "EP_49") (pintype "power_in"))
      (node (ref "U2") (pin "2") (pinfunction "2_2") (pintype "power_in"))
      (node (ref "U2") (pin "5") (pinfunction "5_5") (pintype "power_in"))
      (node (ref "U3") (pin "2") (pinfunction "2_2") (pintype "power_in"))
      (node (ref "U3") (pin "5") (pinfunction "5_5") (pintype "power_in"))
      (node (ref "U4") (pin "6") (pinfunction "V_S-_6") (pintype "power_in"))
      (node (ref "U5") (pin "6") (pinfunction "V_S-_6") (pintype "power_in"))
      (node (ref "U6") (pin "6") (pinfunction "V_S-_6") (pintype "power_in"))
      (node (ref "U7") (pin "6") (pinfunction "V_S-_6") (pintype "power_in"))
      (node (ref "X1") (pin "2@1") (pinfunction "GND_2@1") (pintype "power_in"))
      (node (ref "X1") (pin "2@2") (pinfunction "GND_2@2") (pintype "power_in"))
      (node (ref "X1") (pin "2@3") (pinfunction "GND_2@3") (pintype "power_in"))
      (node (ref "X1") (pin "2@4") (pinfunction "GND_2@4") (pintype "power_in"))
      (node (ref "X1") (pin "2@5") (pinfunction "GND_2@5") (pintype "power_in"))
      (node (ref "X1") (pin "2@6") (pinfunction "GND_2@6") (pintype "power_in"))
      (node (ref "X2") (pin "2@1") (pinfunction "GND_2@1") (pintype "power_in"))
      (node (ref "X2") (pin "2@2") (pinfunction "GND_2@2") (pintype "power_in"))
      (node (ref "X2") (pin "2@3") (pinfunction "GND_2@3") (pintype "power_in"))
      (node (ref "X2") (pin "2@4") (pinfunction "GND_2@4") (pintype "power_in"))
      (node (ref "X2") (pin "2@5") (pinfunction "GND_2@5") (pintype "power_in"))
      (node (ref "X2") (pin "2@6") (pinfunction "GND_2@6") (pintype "power_in"))
      (node (ref "X4") (pin "2@1") (pinfunction "GND_2@1") (pintype "power_in"))
      (node (ref "X4") (pin "2@2") (pinfunction "GND_2@2") (pintype "power_in"))
      (node (ref "X4") (pin "2@3") (pinfunction "GND_2@3") (pintype "power_in"))
      (node (ref "X4") (pin "2@4") (pinfunction "GND_2@4") (pintype "power_in"))
      (node (ref "X4") (pin "2@5") (pinfunction "GND_2@5") (pintype "power_in"))
      (node (ref "X4") (pin "2@6") (pinfunction "GND_2@6") (pintype "power_in"))
      (node (ref "X5") (pin "2@1") (pinfunction "GND_2@1") (pintype "power_in"))
      (node (ref "X5") (pin "2@2") (pinfunction "GND_2@2") (pintype "power_in"))
      (node (ref "X5") (pin "2@3") (pinfunction "GND_2@3") (pintype "power_in"))
      (node (ref "X5") (pin "2@4") (pinfunction "GND_2@4") (pintype "power_in"))
      (node (ref "X5") (pin "2@5") (pinfunction "GND_2@5") (pintype "power_in"))
      (node (ref "X5") (pin "2@6") (pinfunction "GND_2@6") (pintype "power_in"))
      (node (ref "X6") (pin "2@1") (pinfunction "GND_2@1") (pintype "power_in"))
      (node (ref "X6") (pin "2@2") (pinfunction "GND_2@2") (pintype "power_in"))
      (node (ref "X6") (pin "2@3") (pinfunction "GND_2@3") (pintype "power_in"))
      (node (ref "X6") (pin "2@4") (pinfunction "GND_2@4") (pintype "power_in"))
      (node (ref "X6") (pin "2@5") (pinfunction "GND_2@5") (pintype "power_in"))
      (node (ref "X6") (pin "2@6") (pinfunction "GND_2@6") (pintype "power_in"))
      (node (ref "X7") (pin "2@1") (pinfunction "GND_2@1") (pintype "power_in"))
      (node (ref "X7") (pin "2@2") (pinfunction "GND_2@2") (pintype "power_in"))
      (node (ref "X7") (pin "2@3") (pinfunction "GND_2@3") (pintype "power_in"))
      (node (ref "X7") (pin "2@4") (pinfunction "GND_2@4") (pintype "power_in"))
      (node (ref "X7") (pin "2@5") (pinfunction "GND_2@5") (pintype "power_in"))
      (node (ref "X7") (pin "2@6") (pinfunction "GND_2@6") (pintype "power_in"))
    )
    (net (code "11") (name "ANTSEL") (class "Default")
      (node (ref "J1") (pin "19") (pinfunction "19_19") (pintype "passive"))
      (node (ref "U1") (pin "47") (pinfunction "ANTSEL_47") (pintype "input"))
    )
    (net (code "12") (name "BYPASS") (class "Default")
      (node (ref "C117") (pin "1") (pinfunction "1_1") (pintype "passive"))
      (node (ref "U1") (pin "33") (pinfunction "BYPASS_33") (pintype "power_in"))
    )
    (net (code "13") (name "CLK1") (class "Default")
      (node (ref "J1") (pin "12") (pinfunction "12_12") (pintype "passive"))
      (node (ref "U8") (pin "2") (pinfunction "CLK_2") (pintype "input"))
      (node (ref "U9") (pin "2") (pinfunction "Q_2") (pintype "output"))
    )
    (net (code "14") (name "CLK2") (class "Default")
      (node (ref "J1") (pin "14") (pinfunction "14_14") (pintype "passive"))
      (node (ref "U8") (pin "3") (pinfunction "NCLK_3") (pintype "input"))
      (node (ref "U9") (pin "3") (pinfunction "NQ_3") (pintype "output"))
    )
    (net (code "15") (name "D1V5") (class "Default")
      (node (ref "J1") (pin "7") (pinfunction "7_7") (pintype "passive"))
      (node (ref "J1") (pin "8") (pinfunction "8_8") (pintype "passive"))
    )
    (net (code "16") (name "D3V3") (class "Default")
      (node (ref "IC1") (pin "8") (pinfunction "VCC_8") (pintype "power_in"))
      (node (ref "J1") (pin "5") (pinfunction "5_5") (pintype "passive"))
      (node (ref "J1") (pin "6") (pinfunction "6_6") (pintype "passive"))
      (node (ref "R1") (pin "2") (pinfunction "2_2") (pintype "passive"))
      (node (ref "R2") (pin "2") (pinfunction "2_2") (pintype "passive"))
      (node (ref "RA01") (pin "1") (pinfunction "1_1") (pintype "passive"))
      (node (ref "RA11") (pin "1") (pinfunction "1_1") (pintype "passive"))
      (node (ref "RA21") (pin "1") (pinfunction "1_1") (pintype "passive"))
      (node (ref "RWP1") (pin "1") (pinfunction "1_1") (pintype "passive"))
    )
    (net (code "17") (name "DAC3+") (class "Default")
      (node (ref "J1") (pin "58") (pinfunction "58_58") (pintype "passive"))
      (node (ref "R62") (pin "1") (pinfunction "1_1") (pintype "passive"))
    )
    (net (code "18") (name "DAC3-") (class "Default")
      (node (ref "J1") (pin "56") (pinfunction "56_56") (pintype "passive"))
      (node (ref "R61") (pin "1") (pinfunction "1_1") (pintype "passive"))
    )
    (net (code "19") (name "DAC4+") (class "Default")
      (node (ref "J1") (pin "64") (pinfunction "64_64") (pintype "passive"))
      (node (ref "R72") (pin "1") (pinfunction "1_1") (pintype "passive"))
    )
    (net (code "20") (name "DAC4-") (class "Default")
      (node (ref "J1") (pin "62") (pinfunction "62_62") (pintype "passive"))
      (node (ref "R71") (pin "1") (pinfunction "1_1") (pintype "passive"))
    )
    (net (code "21") (name "DGND") (class "Default")
      (node (ref "C123") (pin "2") (pinfunction "2_2") (pintype "passive"))
      (node (ref "C124") (pin "2") (pinfunction "2_2") (pintype "passive"))
      (node (ref "C125") (pin "2") (pinfunction "2_2") (pintype "passive"))
      (node (ref "C126") (pin "2") (pinfunction "2_2") (pintype "passive"))
      (node (ref "C127") (pin "2") (pinfunction "2_2") (pintype "passive"))
      (node (ref "C128") (pin "2") (pinfunction "2_2") (pintype "passive"))
      (node (ref "C129") (pin "2") (pinfunction "2_2") (pintype "passive"))
      (node (ref "C130") (pin "2") (pinfunction "2_2") (pintype "passive"))
      (node (ref "C131") (pin "2") (pinfunction "2_2") (pintype "passive"))
      (node (ref "IC1") (pin "4") (pinfunction "GND_4") (pintype "power_in"))
      (node (ref "J1") (pin "1") (pinfunction "1_1") (pintype "passive"))
      (node (ref "J1") (pin "10") (pinfunction "10_10") (pintype "passive"))
      (node (ref "J1") (pin "15") (pinfunction "15_15") (pintype "passive"))
      (node (ref "J1") (pin "16") (pinfunction "16_16") (pintype "passive"))
      (node (ref "J1") (pin "2") (pinfunction "2_2") (pintype "passive"))
      (node (ref "J1") (pin "9") (pinfunction "9_9") (pintype "passive"))
      (node (ref "R3") (pin "1") (pinfunction "1_1") (pintype "passive"))
      (node (ref "R4") (pin "1") (pinfunction "1_1") (pintype "passive"))
      (node (ref "RA00") (pin "1") (pinfunction "1_1") (pintype "passive"))
      (node (ref "RA10") (pin "1") (pinfunction "1_1") (pintype "passive"))
      (node (ref "RA20") (pin "1") (pinfunction "1_1") (pintype "passive"))
      (node (ref "RWP0") (pin "1") (pinfunction "1_1") (pintype "passive"))
      (node (ref "U8") (pin "5") (pinfunction "GND_5") (pintype "power_in"))
      (node (ref "U9") (pin "5") (pinfunction "VEE_5") (pintype "power_in"))
      (node (ref "X3") (pin "2") (pinfunction "GND_2") (pintype "power_in"))
    )
    (net (code "22") (name "DIN") (class "Default")
      (node (ref "J1") (pin "20") (pinfunction "20_20") (pintype "passive"))
      (node (ref "U1") (pin "19") (pinfunction "DIN_19") (pintype "input"))
    )
    (net (code "23") (name "I2C_SCL") (class "Default")
      (node (ref "IC1") (pin "6") (pinfunction "SCL_6") (pintype "input"))
      (node (ref "J1") (pin "26") (pinfunction "26_26") (pintype "passive"))
      (node (ref "R1") (pin "1") (pinfunction "1_1") (pintype "passive"))
    )
    (net (code "24") (name "I2C_SDA") (class "Default")
      (node (ref "IC1") (pin "5") (pinfunction "SDA_5") (pintype "bidirectional"))
      (node (ref "J1") (pin "28") (pinfunction "28_28") (pintype "passive"))
      (node (ref "R2") (pin "1") (pinfunction "1_1") (pintype "passive"))
    )
    (net (code "25") (name "LD") (class "Default")
      (node (ref "J1") (pin "11") (pinfunction "11_11") (pintype "passive"))
      (node (ref "U1") (pin "22") (pinfunction "LD_22") (pintype "output"))
    )
    (net (code "26") (name "Net-(C64-Pad1)") (class "Default")
      (node (ref "C64") (pin "1") (pinfunction "1_1") (pintype "passive"))
      (node (ref "R65") (pin "2") (pinfunction "2_2") (pintype "passive"))
      (node (ref "R66") (pin "1") (pinfunction "1_1") (pintype "passive"))
    )
    (net (code "27") (name "Net-(C74-Pad1)") (class "Default")
      (node (ref "C74") (pin "1") (pinfunction "1_1") (pintype "passive"))
      (node (ref "R75") (pin "2") (pinfunction "2_2") (pintype "passive"))
      (node (ref "R76") (pin "1") (pinfunction "1_1") (pintype "passive"))
    )
    (net (code "28") (name "Net-(C119-Pad1)") (class "Default")
      (node (ref "C119") (pin "1") (pinfunction "1_1") (pintype "passive"))
      (node (ref "R102") (pin "2") (pinfunction "2_2") (pintype "passive"))
    )
    (net (code "29") (name "Net-(R41-Pad2)") (class "Default")
      (node (ref "R41") (pin "2") (pinfunction "2_2") (pintype "passive"))
      (node (ref "R43") (pin "1") (pinfunction "1_1") (pintype "passive"))
      (node (ref "X4") (pin "1") (pinfunction "1_1") (pintype "passive"))
    )
    (net (code "30") (name "Net-(R42-Pad2)") (class "Default")
      (node (ref "R42") (pin "2") (pinfunction "2_2") (pintype "passive"))
      (node (ref "R44") (pin "1") (pinfunction "1_1") (pintype "passive"))
    )
    (net (code "31") (name "Net-(R51-Pad2)") (class "Default")
      (node (ref "R51") (pin "2") (pinfunction "2_2") (pintype "passive"))
      (node (ref "R53") (pin "1") (pinfunction "1_1") (pintype "passive"))
      (node (ref "X5") (pin "1") (pinfunction "1_1") (pintype "passive"))
    )
    (net (code "32") (name "Net-(R52-Pad2)") (class "Default")
      (node (ref "R52") (pin "2") (pinfunction "2_2") (pintype "passive"))
      (node (ref "R54") (pin "1") (pinfunction "1_1") (pintype "passive"))
    )
    (net (code "33") (name "Net-(R66-Pad2)") (class "Default")
      (node (ref "R66") (pin "2") (pinfunction "2_2") (pintype "passive"))
      (node (ref "X6") (pin "1") (pinfunction "1_1") (pintype "passive"))
    )
    (net (code "34") (name "Net-(R76-Pad2)") (class "Default")
      (node (ref "R76") (pin "2") (pinfunction "2_2") (pintype "passive"))
      (node (ref "X7") (pin "1") (pinfunction "1_1") (pintype "passive"))
    )
    (net (code "35") (name "Net-(U1A-ANT1+)") (class "Default")
      (node (ref "U1") (pin "4") (pinfunction "ANT1+_4") (pintype "bidirectional"))
      (node (ref "U2") (pin "4") (pinfunction "4_4") (pintype "bidirectional"))
    )
    (net (code "36") (name "Net-(U1A-ANT1-)") (class "Default")
      (node (ref "U1") (pin "5") (pinfunction "ANT1-_5") (pintype "bidirectional"))
      (node (ref "U2") (pin "3") (pinfunction "3_3") (pintype "bidirectional"))
    )
    (net (code "37") (name "Net-(U1A-ANT2+)") (class "Default")
      (node (ref "U1") (pin "9") (pinfunction "ANT2+_9") (pintype "bidirectional"))
      (node (ref "U3") (pin "4") (pinfunction "4_4") (pintype "bidirectional"))
    )
    (net (code "38") (name "Net-(U1A-ANT2-)") (class "Default")
      (node (ref "U1") (pin "10") (pinfunction "ANT2-_10") (pintype "bidirectional"))
      (node (ref "U3") (pin "3") (pinfunction "3_3") (pintype "bidirectional"))
    )
    (net (code "39") (name "Net-(U1D-CPOUT)") (class "Default")
      (node (ref "C120") (pin "1") (pinfunction "1_1") (pintype "passive"))
      (node (ref "R101") (pin "1") (pinfunction "1_1") (pintype "passive"))
      (node (ref "R102") (pin "1") (pinfunction "1_1") (pintype "passive"))
      (node (ref "U1") (pin "24") (pinfunction "CPOUT_24") (pintype "output"))
    )
    (net (code "40") (name "Net-(U1D-CTUNE)") (class "Default")
      (node (ref "C121") (pin "1") (pinfunction "1_1") (pintype "passive"))
      (node (ref "U1") (pin "29") (pinfunction "CTUNE_29") (pintype "input"))
    )
    (net (code "41") (name "Net-(U1D-TUNE)") (class "Default")
      (node (ref "C118") (pin "1") (pinfunction "1_1") (pintype "passive"))
      (node (ref "R101") (pin "2") (pinfunction "2_2") (pintype "passive"))
      (node (ref "U1") (pin "32") (pinfunction "TUNE_32") (pintype "input"))
    )
    (net (code "42") (name "Net-(U2-Pad1)") (class "Default")
      (node (ref "U2") (pin "1") (pinfunction "1_1") (pintype "bidirectional"))
      (node (ref "X1") (pin "1") (pinfunction "1_1") (pintype "passive"))
    )
    (net (code "43") (name "Net-(U3-Pad1)") (class "Default")
      (node (ref "U3") (pin "1") (pinfunction "1_1") (pintype "bidirectional"))
      (node (ref "X2") (pin "1") (pinfunction "1_1") (pintype "passive"))
    )
    (net (code "44") (name "Net-(U4-+IN)") (class "Default")
      (node (ref "R43") (pin "2") (pinfunction "2_2") (pintype "passive"))
      (node (ref "R45") (pin "1") (pinfunction "1_1") (pintype "passive"))
      (node (ref "U4") (pin "8") (pinfunction "+IN_8") (pintype "input"))
    )
    (net (code "45") (name "Net-(U4-+OUT)") (class "Default")
      (node (ref "R46") (pin "2") (pinfunction "2_2") (pintype "passive"))
      (node (ref "R48") (pin "1") (pinfunction "1_1") (pintype "passive"))
      (node (ref "U4") (pin "4") (pinfunction "+OUT_4") (pintype "output"))
    )
    (net (code "46") (name "Net-(U4--IN)") (class "Default")
      (node (ref "R44") (pin "2") (pinfunction "2_2") (pintype "passive"))
      (node (ref "R46") (pin "1") (pinfunction "1_1") (pintype "passive"))
      (node (ref "U4") (pin "1") (pinfunction "-IN_1") (pintype "input"))
    )
    (net (code "47") (name "Net-(U4--OUT)") (class "Default")
      (node (ref "R45") (pin "2") (pinfunction "2_2") (pintype "passive"))
      (node (ref "R47") (pin "1") (pinfunction "1_1") (pintype "passive"))
      (node (ref "U4") (pin "5") (pinfunction "-OUT_5") (pintype "output"))
    )
    (net (code "48") (name "Net-(U5-+IN)") (class "Default")
      (node (ref "R53") (pin "2") (pinfunction "2_2") (pintype "passive"))
      (node (ref "R55") (pin "1") (pinfunction "1_1") (pintype "passive"))
      (node (ref "U5") (pin "8") (pinfunction "+IN_8") (pintype "input"))
    )
    (net (code "49") (name "Net-(U5-+OUT)") (class "Default")
      (node (ref "R56") (pin "2") (pinfunction "2_2") (pintype "passive"))
      (node (ref "R58") (pin "1") (pinfunction "1_1") (pintype "passive"))
      (node (ref "U5") (pin "4") (pinfunction "+OUT_4") (pintype "output"))
    )
    (net (code "50") (name "Net-(U5--IN)") (class "Default")
      (node (ref "R54") (pin "2") (pinfunction "2_2") (pintype "passive"))
      (node (ref "R56") (pin "1") (pinfunction "1_1") (pintype "passive"))
      (node (ref "U5") (pin "1") (pinfunction "-IN_1") (pintype "input"))
    )
    (net (code "51") (name "Net-(U5--OUT)") (class "Default")
      (node (ref "R55") (pin "2") (pinfunction "2_2") (pintype "passive"))
      (node (ref "R57") (pin "1") (pinfunction "1_1") (pintype "passive"))
      (node (ref "U5") (pin "5") (pinfunction "-OUT_5") (pintype "output"))
    )
    (net (code "52") (name "Net-(U6-+IN)") (class "Default")
      (node (ref "R61") (pin "2") (pinfunction "2_2") (pintype "passive"))
      (node (ref "R63") (pin "1") (pinfunction "1_1") (pintype "passive"))
      (node (ref "U6") (pin "8") (pinfunction "+IN_8") (pintype "input"))
    )
    (net (code "53") (name "Net-(U6-+OUT)") (class "Default")
      (node (ref "R64") (pin "2") (pinfunction "2_2") (pintype "passive"))
      (node (ref "U6") (pin "4") (pinfunction "+OUT_4") (pintype "output"))
    )
    (net (code "54") (name "Net-(U6--IN)") (class "Default")
      (node (ref "R62") (pin "2") (pinfunction "2_2") (pintype "passive"))
      (node (ref "R64") (pin "1") (pinfunction "1_1") (pintype "passive"))
      (node (ref "U6") (pin "1") (pinfunction "-IN_1") (pintype "input"))
    )
    (net (code "55") (name "Net-(U6--OUT)") (class "Default")
      (node (ref "R63") (pin "2") (pinfunction "2_2") (pintype "passive"))
      (node (ref "R65") (pin "1") (pinfunction "1_1") (pintype "passive"))
      (node (ref "U6") (pin "5") (pinfunction "-OUT_5") (pintype "output"))
    )
    (net (code "56") (name "Net-(U7-+IN)") (class "Default")
      (node (ref "R71") (pin "2") (pinfunction "2_2") (pintype "passive"))
      (node (ref "R73") (pin "1") (pinfunction "1_1") (pintype "passive"))
      (node (ref "U7") (pin "8") (pinfunction "+IN_8") (pintype "input"))
    )
    (net (code "57") (name "Net-(U7-+OUT)") (class "Default")
      (node (ref "R74") (pin "2") (pinfunction "2_2") (pintype "passive"))
      (node (ref "U7") (pin "4") (pinfunction "+OUT_4") (pintype "output"))
    )
    (net (code "58") (name "Net-(U7--IN)") (class "Default")
      (node (ref "R72") (pin "2") (pinfunction "2_2") (pintype "passive"))
      (node (ref "R74") (pin "1") (pinfunction "1_1") (pintype "passive"))
      (node (ref "U7") (pin "1") (pinfunction "-IN_1") (pintype "input"))
    )
    (net (code "59") (name "Net-(U7--OUT)") (class "Default")
      (node (ref "R73") (pin "2") (pinfunction "2_2") (pintype "passive"))
      (node (ref "R75") (pin "1") (pinfunction "1_1") (pintype "passive"))
      (node (ref "U7") (pin "5") (pinfunction "-OUT_5") (pintype "output"))
    )
    (net (code "60") (name "Net-(U8-Q0)") (class "Default")
      (node (ref "C121") (pin "2") (pinfunction "2_2") (pintype "passive"))
      (node (ref "C122") (pin "2") (pinfunction "2_2") (pintype "passive"))
      (node (ref "U8") (pin "7") (pinfunction "Q0_7") (pintype "output"))
      (node (ref "X3") (pin "3") (pinfunction "FO_3") (pintype "output"))
    )
    (net (code "61") (name "Net-(U9-CLK)") (class "Default")
      (node (ref "C122") (pin "1") (pinfunction "1_1") (pintype "passive"))
      (node (ref "U9") (pin "7") (pinfunction "CLK_7") (pintype "input"))
    )
    (net (code "62") (name "RSSI") (class "Default")
      (node (ref "J1") (pin "39") (pinfunction "39_39") (pintype "passive"))
      (node (ref "U1") (pin "16") (pinfunction "RSSI_16") (pintype "output"))
    )
    (net (code "63") (name "RXBBI+") (class "Default")
      (node (ref "J1") (pin "52") (pinfunction "52_52") (pintype "passive"))
      (node (ref "U1") (pin "38") (pinfunction "RXBBI+_38") (pintype "output"))
    )
    (net (code "64") (name "RXBBI-") (class "Default")
      (node (ref "J1") (pin "50") (pinfunction "50_50") (pintype "passive"))
      (node (ref "U1") (pin "37") (pinfunction "RXBBI-_37") (pintype "output"))
    )
    (net (code "65") (name "RXBBQ+") (class "Default")
      (node (ref "J1") (pin "46") (pinfunction "46_46") (pintype "passive"))
      (node (ref "U1") (pin "36") (pinfunction "RXBBQ+_36") (pintype "output"))
    )
    (net (code "66") (name "RXBBQ-") (class "Default")
      (node (ref "J1") (pin "44") (pinfunction "44_44") (pintype "passive"))
      (node (ref "U1") (pin "35") (pinfunction "RXBBQ-_35") (pintype "output"))
    )
    (net (code "67") (name "RXHP") (class "Default")
      (node (ref "J1") (pin "17") (pinfunction "17_17") (pintype "passive"))
      (node (ref "U1") (pin "40") (pinfunction "RXHP_40") (pintype "input"))
    )
    (net (code "68") (name "RXTX") (class "Default")
      (node (ref "J1") (pin "21") (pinfunction "21_21") (pintype "passive"))
      (node (ref "U1") (pin "48") (pinfunction "RXTX_48") (pintype "input"))
    )
    (net (code "69") (name "SCLK") (class "Default")
      (node (ref "J1") (pin "18") (pinfunction "18_18") (pintype "passive"))
      (node (ref "U1") (pin "18") (pinfunction "SCLK_18") (pintype "input"))
    )
    (net (code "70") (name "TXBBI+") (class "Default")
      (node (ref "J1") (pin "40") (pinfunction "40_40") (pintype "passive"))
      (node (ref "U1") (pin "45") (pinfunction "TXBBI+_45") (pintype "input"))
    )
    (net (code "71") (name "TXBBI-") (class "Default")
      (node (ref "J1") (pin "38") (pinfunction "38_38") (pintype "passive"))
      (node (ref "U1") (pin "44") (pinfunction "TXBBI-_44") (pintype "input"))
    )
    (net (code "72") (name "TXBBQ+") (class "Default")
      (node (ref "J1") (pin "34") (pinfunction "34_34") (pintype "passive"))
      (node (ref "U1") (pin "43") (pinfunction "TXBBQ+_43") (pintype "input"))
    )
    (net (code "73") (name "TXBBQ-") (class "Default")
      (node (ref "J1") (pin "32") (pinfunction "32_32") (pintype "passive"))
      (node (ref "U1") (pin "42") (pinfunction "TXBBQ-_42") (pintype "input"))
    )
    (net (code "74") (name "VSUP") (class "Default")
      (node (ref "J1") (pin "3") (pinfunction "3_3") (pintype "passive"))
      (node (ref "J1") (pin "4") (pinfunction "4_4") (pintype "passive"))
    )
    (net (code "75") (name "V_BIAS_ADC") (class "Default")
      (node (ref "C45") (pin "1") (pinfunction "1_1") (pintype "passive"))
      (node (ref "R451") (pin "1") (pinfunction "1_1") (pintype "passive"))
      (node (ref "R452") (pin "2") (pinfunction "2_2") (pintype "passive"))
      (node (ref "U4") (pin "2") (pinfunction "V_OCM_2") (pintype "input"))
      (node (ref "U5") (pin "2") (pinfunction "V_OCM_2") (pintype "input"))
    )
    (net (code "76") (name "V_BIAS_DAC") (class "Default")
      (node (ref "C67") (pin "1") (pinfunction "1_1") (pintype "passive"))
      (node (ref "R671") (pin "1") (pinfunction "1_1") (pintype "passive"))
      (node (ref "R672") (pin "2") (pinfunction "2_2") (pintype "passive"))
      (node (ref "U6") (pin "2") (pinfunction "V_OCM_2") (pintype "input"))
      (node (ref "U7") (pin "2") (pinfunction "V_OCM_2") (pintype "input"))
    )
    (net (code "77") (name "WP") (class "Default")
      (node (ref "IC1") (pin "7") (pinfunction "WP_7") (pintype "input"))
      (node (ref "RWP0") (pin "2") (pinfunction "2_2") (pintype "passive"))
      (node (ref "RWP1") (pin "2") (pinfunction "2_2") (pintype "passive"))
    )
    (net (code "78") (name "unconnected-(J1-Pad22)") (class "Default")
      (node (ref "J1") (pin "22") (pinfunction "22_22") (pintype "passive"))
    )
    (net (code "79") (name "unconnected-(J1-Pad23)") (class "Default")
      (node (ref "J1") (pin "23") (pinfunction "23_23") (pintype "passive"))
    )
    (net (code "80") (name "unconnected-(J1-Pad25)") (class "Default")
      (node (ref "J1") (pin "25") (pinfunction "25_25") (pintype "passive"))
    )
    (net (code "81") (name "unconnected-(J1-Pad27)") (class "Default")
      (node (ref "J1") (pin "27") (pinfunction "27_27") (pintype "passive"))
    )
    (net (code "82") (name "unconnected-(J1-Pad31)") (class "Default")
      (node (ref "J1") (pin "31") (pinfunction "31_31") (pintype "passive"))
    )
    (net (code "83") (name "unconnected-(J1-Pad33)") (class "Default")
      (node (ref "J1") (pin "33") (pinfunction "33_33") (pintype "passive"))
    )
    (net (code "84") (name "unconnected-(J1-Pad37)") (class "Default")
      (node (ref "J1") (pin "37") (pinfunction "37_37") (pintype "passive"))
    )
    (net (code "85") (name "unconnected-(J1-Pad43)") (class "Default")
      (node (ref "J1") (pin "43") (pinfunction "43_43") (pintype "passive"))
    )
    (net (code "86") (name "unconnected-(J1-Pad45)") (class "Default")
      (node (ref "J1") (pin "45") (pinfunction "45_45") (pintype "passive"))
    )
    (net (code "87") (name "unconnected-(J1-Pad49)") (class "Default")
      (node (ref "J1") (pin "49") (pinfunction "49_49") (pintype "passive"))
    )
    (net (code "88") (name "unconnected-(J1-Pad51)") (class "Default")
      (node (ref "J1") (pin "51") (pinfunction "51_51") (pintype "passive"))
    )
    (net (code "89") (name "unconnected-(J1-Pad55)") (class "Default")
      (node (ref "J1") (pin "55") (pinfunction "55_55") (pintype "passive"))
    )
    (net (code "90") (name "unconnected-(J1-Pad57)") (class "Default")
      (node (ref "J1") (pin "57") (pinfunction "57_57") (pintype "passive"))
    )
    (net (code "91") (name "unconnected-(J1-Pad61)") (class "Default")
      (node (ref "J1") (pin "61") (pinfunction "61_61") (pintype "passive"))
    )
    (net (code "92") (name "unconnected-(J1-Pad63)") (class "Default")
      (node (ref "J1") (pin "63") (pinfunction "63_63") (pintype "passive"))
    )
    (net (code "93") (name "unconnected-(J1-Pad67)") (class "Default")
      (node (ref "J1") (pin "67") (pinfunction "67_67") (pintype "passive"))
    )
    (net (code "94") (name "unconnected-(J1-Pad69)") (class "Default")
      (node (ref "J1") (pin "69") (pinfunction "69_69") (pintype "passive"))
    )
    (net (code "95") (name "unconnected-(J1-Pad73)") (class "Default")
      (node (ref "J1") (pin "73") (pinfunction "73_73") (pintype "passive"))
    )
    (net (code "96") (name "unconnected-(J1-Pad75)") (class "Default")
      (node (ref "J1") (pin "75") (pinfunction "75_75") (pintype "passive"))
    )
    (net (code "97") (name "unconnected-(U1C-B1-Pad23)") (class "Default")
      (node (ref "U1") (pin "23") (pinfunction "B1_23") (pintype "input"))
    )
    (net (code "98") (name "unconnected-(U1C-B2-Pad11)") (class "Default")
      (node (ref "U1") (pin "11") (pinfunction "B2_11") (pintype "input"))
    )
    (net (code "99") (name "unconnected-(U1C-B3-Pad8)") (class "Default")
      (node (ref "U1") (pin "8") (pinfunction "B3_8") (pintype "input"))
    )
    (net (code "100") (name "unconnected-(U1C-B4-Pad34)") (class "Default")
      (node (ref "U1") (pin "34") (pinfunction "B4_34") (pintype "input"))
    )
    (net (code "101") (name "unconnected-(U1C-B5-Pad14)") (class "Default")
      (node (ref "U1") (pin "14") (pinfunction "B5_14") (pintype "input"))
    )
    (net (code "102") (name "unconnected-(U1C-B6-Pad3)") (class "Default")
      (node (ref "U1") (pin "3") (pinfunction "B6_3") (pintype "input"))
    )
    (net (code "103") (name "unconnected-(U1C-B7-Pad6)") (class "Default")
      (node (ref "U1") (pin "6") (pinfunction "B7_6") (pintype "input"))
    )
    (net (code "104") (name "unconnected-(U1D-CLOCKOUT-Pad21)") (class "Default")
      (node (ref "U1") (pin "21") (pinfunction "CLOCKOUT_21") (pintype "output"))
    )
    (net (code "105") (name "unconnected-(U1D-XTAL-Pad28)") (class "Default")
      (node (ref "U1") (pin "28") (pinfunction "XTAL_28") (pintype "input"))
    )
    (net (code "106") (name "unconnected-(U2-Pad6)") (class "Default")
      (node (ref "U2") (pin "6") (pinfunction "6_6") (pintype "no_connect"))
    )
    (net (code "107") (name "unconnected-(U3-Pad6)") (class "Default")
      (node (ref "U3") (pin "6") (pinfunction "6_6") (pintype "no_connect"))
    )
    (net (code "108") (name "unconnected-(U4-PD-Pad7)") (class "Default")
      (node (ref "U4") (pin "7") (pinfunction "PD_7") (pintype "input"))
    )
    (net (code "109") (name "unconnected-(U5-PD-Pad7)") (class "Default")
      (node (ref "U5") (pin "7") (pinfunction "PD_7") (pintype "input"))
    )
    (net (code "110") (name "unconnected-(U6-PD-Pad7)") (class "Default")
      (node (ref "U6") (pin "7") (pinfunction "PD_7") (pintype "input"))
    )
    (net (code "111") (name "unconnected-(U7-PD-Pad7)") (class "Default")
      (node (ref "U7") (pin "7") (pinfunction "PD_7") (pintype "input"))
    )
    (net (code "112") (name "unconnected-(U8-NC-Pad1)") (class "Default")
      (node (ref "U8") (pin "1") (pinfunction "NC_1") (pintype "no_connect"))
    )
    (net (code "113") (name "unconnected-(U8-NC-Pad4)") (class "Default")
      (node (ref "U8") (pin "4") (pinfunction "NC_4") (pintype "no_connect"))
    )
    (net (code "114") (name "unconnected-(U8-NC-Pad6)") (class "Default")
      (node (ref "U8") (pin "6") (pinfunction "NC_6") (pintype "no_connect"))
    )
    (net (code "115") (name "unconnected-(U9-NC-Pad1)") (class "Default")
      (node (ref "U9") (pin "1") (pinfunction "NC_1") (pintype "no_connect"))
    )
    (net (code "116") (name "unconnected-(U9-NC-Pad4)") (class "Default")
      (node (ref "U9") (pin "4") (pinfunction "NC_4") (pintype "no_connect"))
    )
    (net (code "117") (name "unconnected-(U9-NC-Pad6)") (class "Default")
      (node (ref "U9") (pin "6") (pinfunction "NC_6") (pintype "no_connect"))
    )
    (net (code "118") (name "unconnected-(X3-NC-Pad1)") (class "Default")
      (node (ref "X3") (pin "1") (pinfunction "NC_1") (pintype "no_connect"))
    )
    (net (code "119") (name "~{CS}") (class "Default")
      (node (ref "J1") (pin "24") (pinfunction "24_24") (pintype "passive"))
      (node (ref "U1") (pin "15") (pinfunction "/CS_15") (pintype "input"))
    )
    (net (code "120") (name "~{SHDN}") (class "Default")
      (node (ref "J1") (pin "13") (pinfunction "13_13") (pintype "passive"))
      (node (ref "U1") (pin "12") (pinfunction "/SHDN_12") (pintype "input"))
    )
  )
)
